# processor.net
KiCad netlist of a schematic drawn in Altium Designer
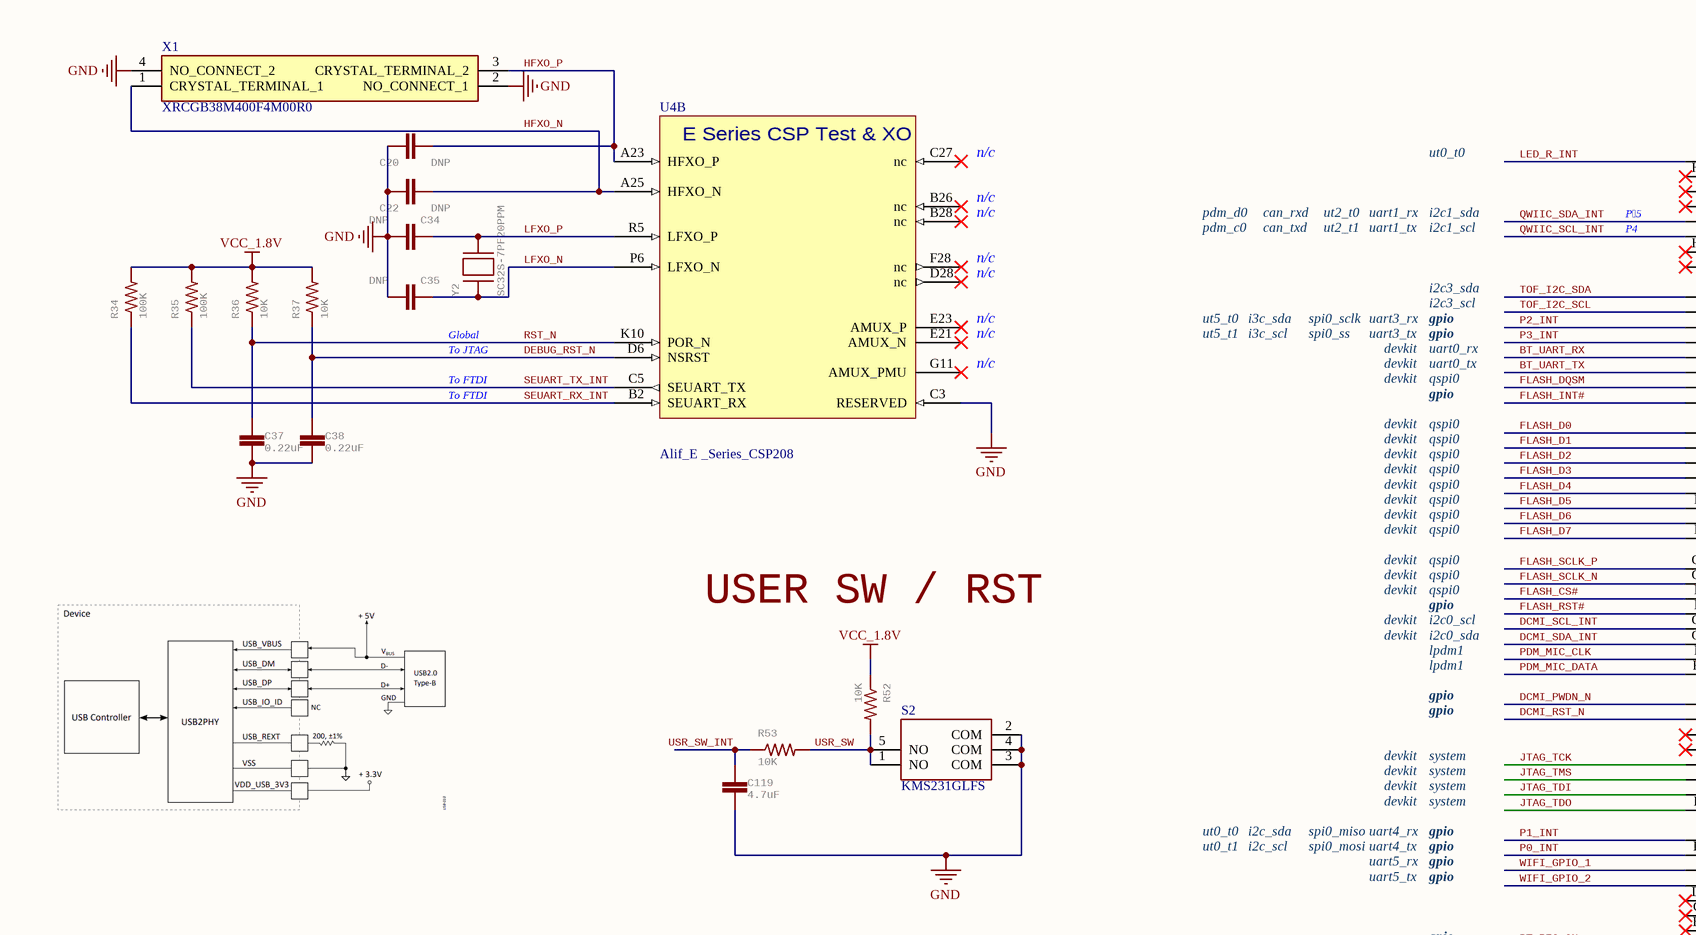
[diagram p0: processor.SchDoc, top left]
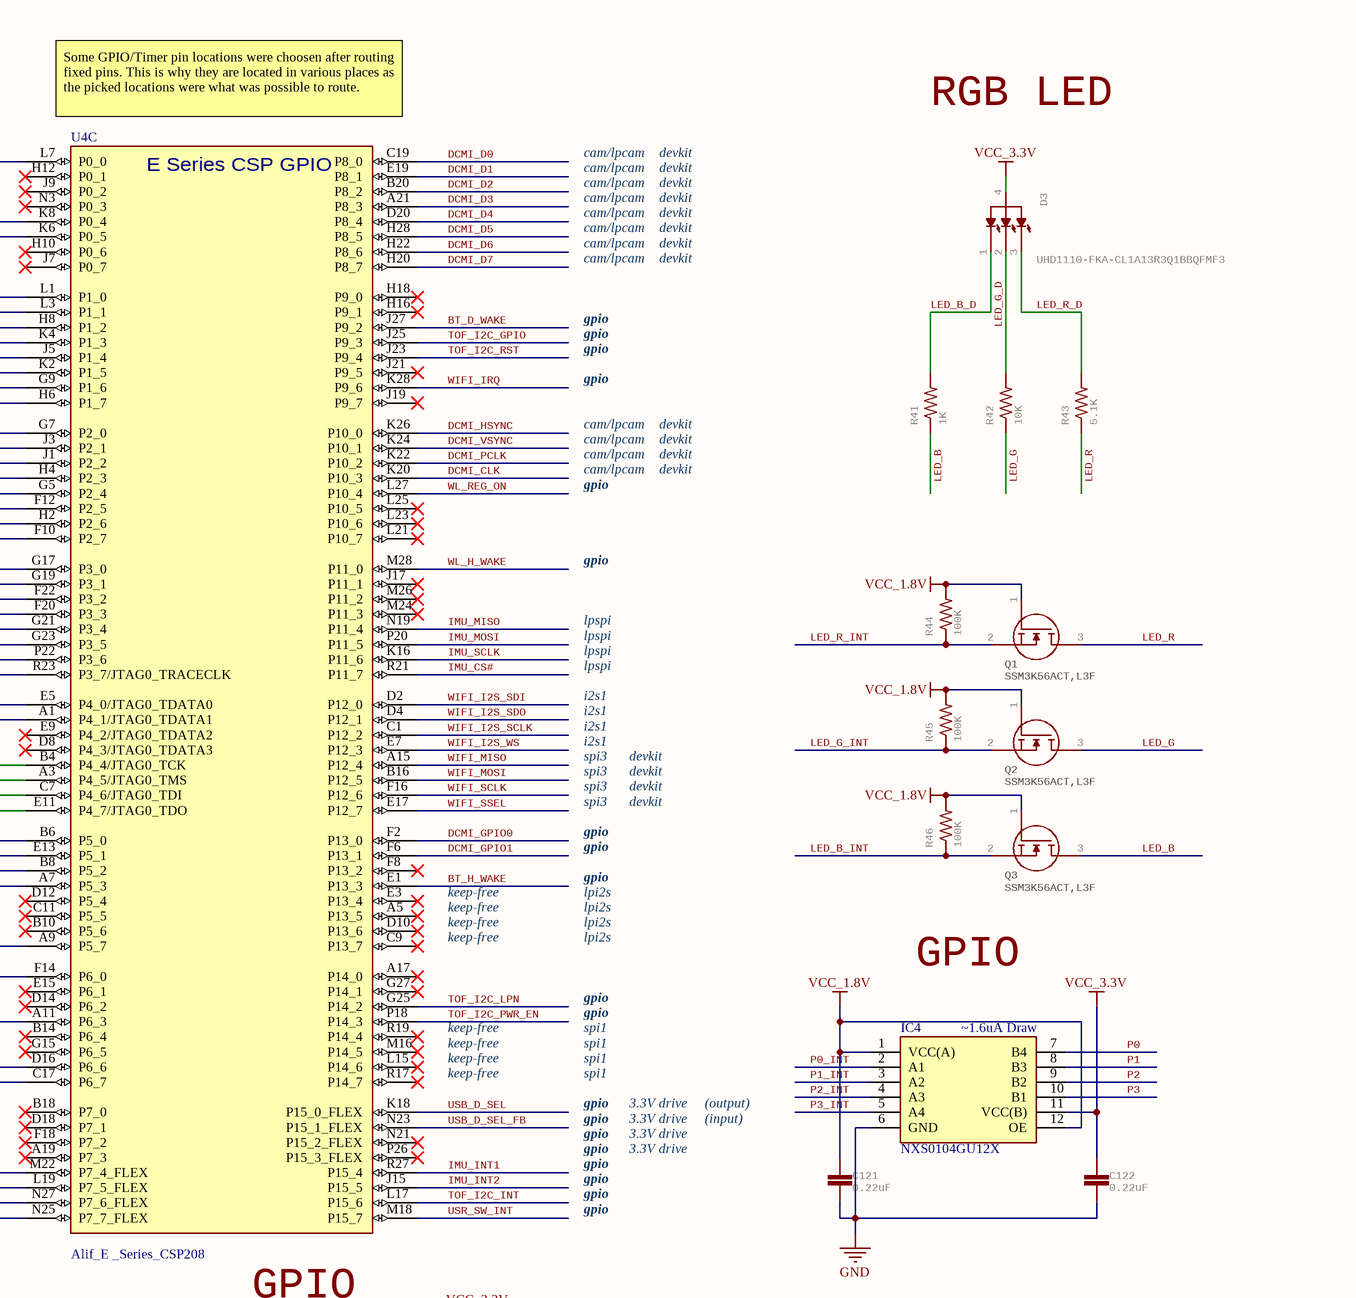
[diagram p1: processor.SchDoc, top right]
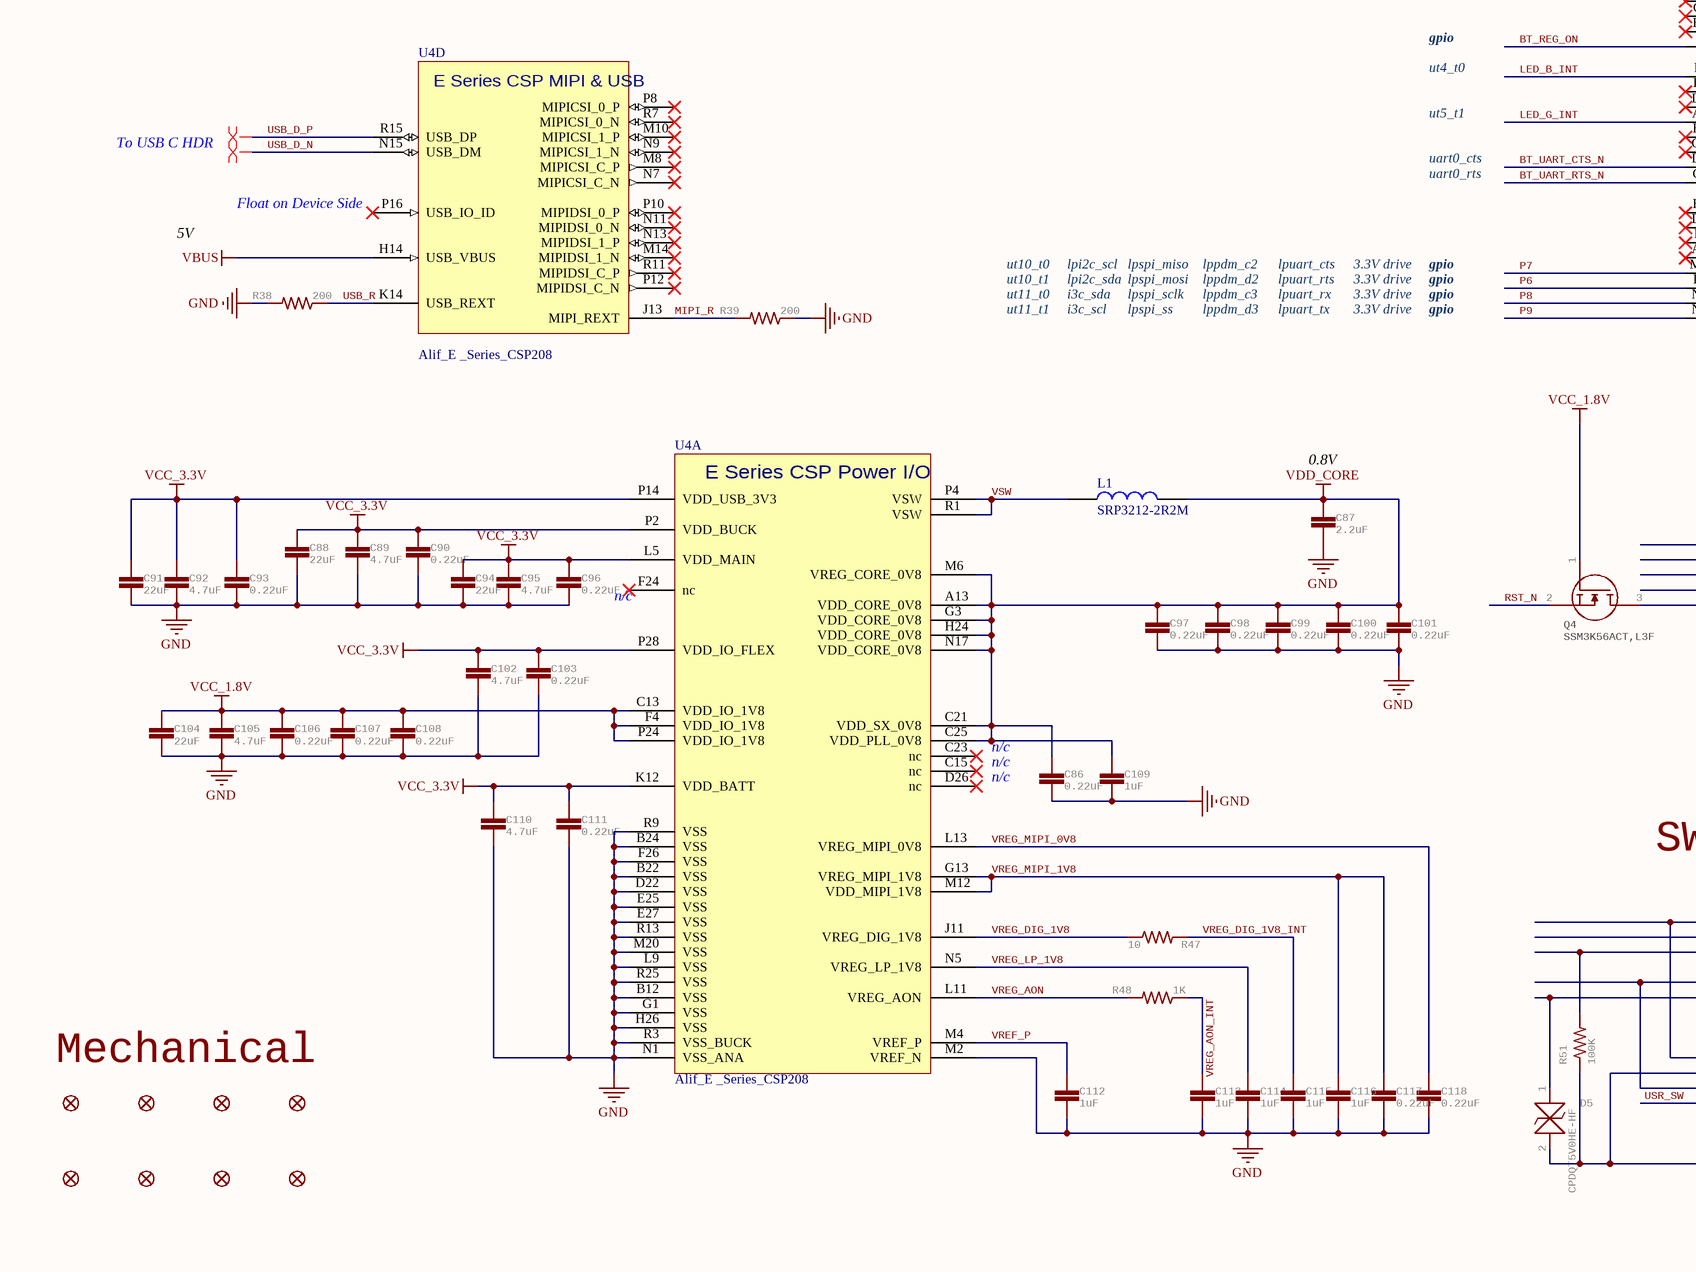
[diagram p2: processor.SchDoc, bottom left]
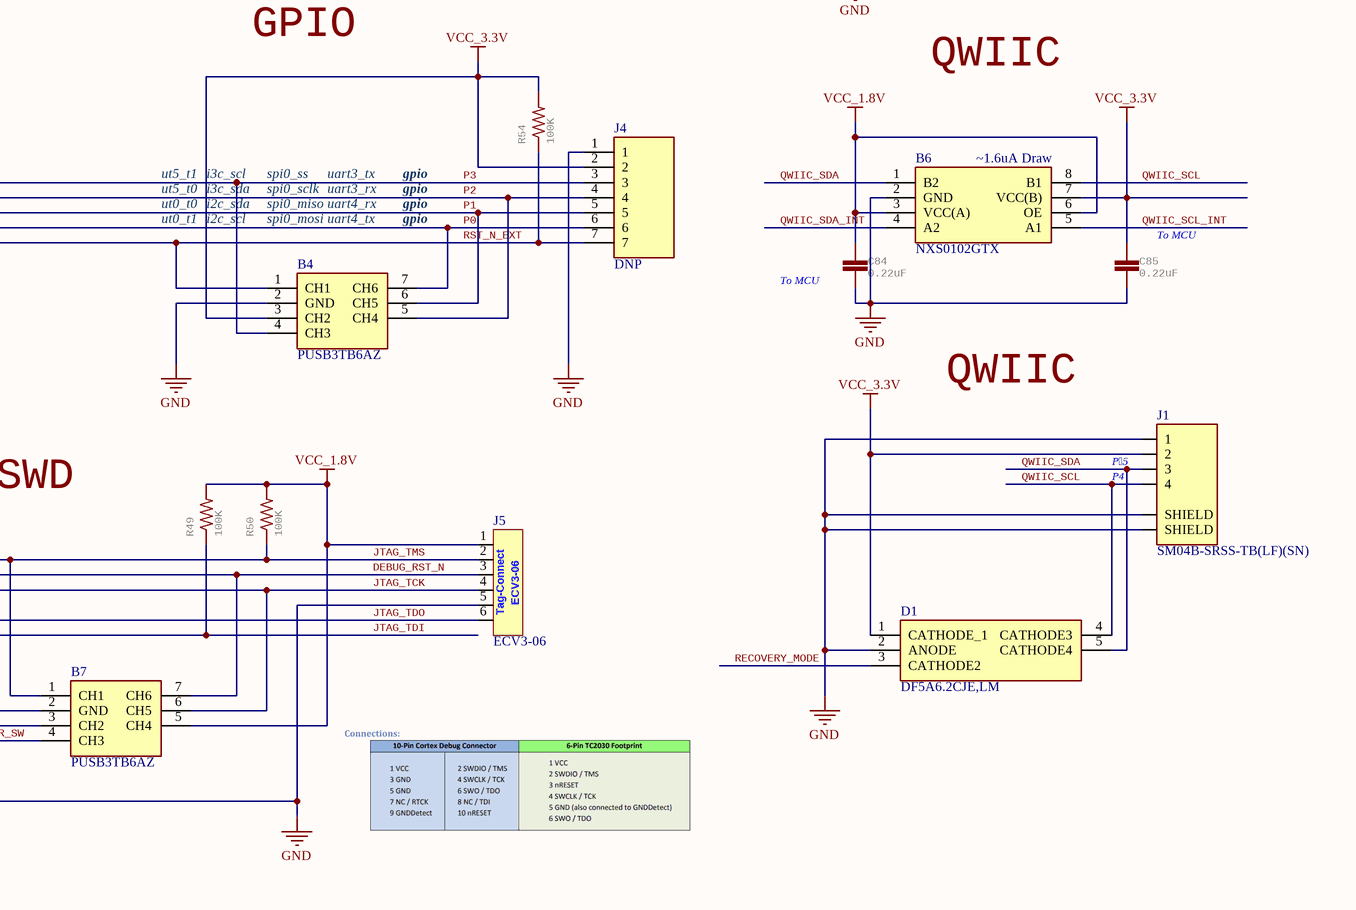
[diagram p3: processor.SchDoc, bottom right]

(export (version "E")
  (design (tool "Eeschema 10.0.6"))
  (components
    (comp (ref "B4")
      (value "PUSB3TB6AZ")
      (footprint "PUSB3TB6AZ")
      (description "NEXPERIA - PUSB3TB6AZ - DIODE, ESD PROTECTION, 5.5V, 0.27PF")
      (fields (field (name "MOUSER PART NUMBER") "771-PUSB3TB6AZ"))
      (libsource (lib "openmv-ae3") (part "PUSB3TB6AZ"))
    )
    (comp (ref "B6")
      (value "NXS0102GTX")
      (footprint "NXS0102GTX")
      (description "Dual supply translating transceiver; open drain; auto direction sensing")
      (fields (field (name "MOUSER PART NUMBER") "771-NXS0102GTX"))
      (libsource (lib "openmv-ae3") (part "NXS0102GTX"))
    )
    (comp (ref "B7")
      (value "PUSB3TB6AZ")
      (footprint "PUSB3TB6AZ")
      (description "NEXPERIA - PUSB3TB6AZ - DIODE, ESD PROTECTION, 5.5V, 0.27PF")
      (fields (field (name "MOUSER PART NUMBER") "771-PUSB3TB6AZ"))
      (libsource (lib "openmv-ae3") (part "PUSB3TB6AZ"))
    )
    (comp (ref "C20")
      (value "DNP")
      (footprint "C0201")
      (description "CAPACITOR, European symbol")
      (libsource (lib "") (part "C-EUC0201_2"))
    )
    (comp (ref "C22")
      (value "DNP")
      (footprint "C0201")
      (description "CAPACITOR, European symbol")
      (libsource (lib "") (part "C-EUC0201_2"))
    )
    (comp (ref "C34")
      (value "DNP")
      (footprint "C0201")
      (description "CAPACITOR, European symbol")
      (libsource (lib "") (part "C-EUC0201_1"))
    )
    (comp (ref "C35")
      (value "DNP")
      (footprint "C0201")
      (description "CAPACITOR, European symbol")
      (libsource (lib "") (part "C-EUC0201_1"))
    )
    (comp (ref "C37")
      (value "0.22uF")
      (footprint "C0201")
      (description "CAPACITOR, European symbol")
      (fields (field (name "MPN") "GRM033R60J224ME15D"))
      (libsource (lib "openmv-ae3") (part "C-EUC0201"))
    )
    (comp (ref "C38")
      (value "0.22uF")
      (footprint "C0201")
      (description "CAPACITOR, European symbol")
      (fields (field (name "MPN") "GRM033R60J224ME15D"))
      (libsource (lib "openmv-ae3") (part "C-EUC0201"))
    )
    (comp (ref "C84")
      (value "0.22uF")
      (footprint "C0201")
      (description "CAPACITOR, European symbol")
      (fields (field (name "MPN") "GRM033R60J224ME15D"))
      (libsource (lib "openmv-ae3") (part "C-EUC0201"))
    )
    (comp (ref "C85")
      (value "0.22uF")
      (footprint "C0201")
      (description "CAPACITOR, European symbol")
      (fields (field (name "MPN") "GRM033R60J224ME15D"))
      (libsource (lib "openmv-ae3") (part "C-EUC0201"))
    )
    (comp (ref "C86")
      (value "0.22uF")
      (footprint "C0201")
      (description "CAPACITOR, European symbol")
      (fields (field (name "MPN") "GRM033R60J224ME15D"))
      (libsource (lib "") (part "C-EUC0201_3"))
    )
    (comp (ref "C87")
      (value "2.2uF")
      (footprint "0402-CAP")
      (description "CapacitorStandard 0603 ceramic capacitor, and 0.1\" leaded capacitor.")
      (fields (field (name "MPN") "CL05A225MQ5NNNC") (field (name "LIBRARYNAME") "sfe"))
      (libsource (lib "openmv-ae3") (part "CAP0402-CAP"))
    )
    (comp (ref "C88")
      (value "22uF")
      (footprint "0805")
      (fields (field (name "MPN") "CL21A226MQQNNNE"))
      (libsource (lib "openmv-ae3") (part "22UF-0805-6.3V-20%"))
    )
    (comp (ref "C89")
      (value "4.7uF")
      (footprint "0402-CAP")
      (description "CapacitorStandard 0603 ceramic capacitor, and 0.1\" leaded capacitor.")
      (fields (field (name "MPN") "JMK105BBJ475MV-F") (field (name "LIBRARYNAME") "sfe"))
      (libsource (lib "openmv-ae3") (part "CAP0402-CAP"))
    )
    (comp (ref "C90")
      (value "0.22uF")
      (footprint "C0201")
      (description "CAPACITOR, European symbol")
      (fields (field (name "MPN") "GRM033R60J224ME15D"))
      (libsource (lib "openmv-ae3") (part "C-EUC0201"))
    )
    (comp (ref "C91")
      (value "22uF")
      (footprint "0805")
      (fields (field (name "MPN") "CL21A226MQQNNNE"))
      (libsource (lib "openmv-ae3") (part "22UF-0805-6.3V-20%"))
    )
    (comp (ref "C92")
      (value "4.7uF")
      (footprint "0402-CAP")
      (description "CapacitorStandard 0603 ceramic capacitor, and 0.1\" leaded capacitor.")
      (fields (field (name "MPN") "JMK105BBJ475MV-F") (field (name "LIBRARYNAME") "sfe"))
      (libsource (lib "openmv-ae3") (part "CAP0402-CAP"))
    )
    (comp (ref "C93")
      (value "0.22uF")
      (footprint "C0201")
      (description "CAPACITOR, European symbol")
      (fields (field (name "MPN") "GRM033R60J224ME15D"))
      (libsource (lib "openmv-ae3") (part "C-EUC0201"))
    )
    (comp (ref "C94")
      (value "22uF")
      (footprint "0805")
      (fields (field (name "MPN") "CL21A226MQQNNNE"))
      (libsource (lib "openmv-ae3") (part "22UF-0805-6.3V-20%"))
    )
    (comp (ref "C95")
      (value "4.7uF")
      (footprint "0402-CAP")
      (description "CapacitorStandard 0603 ceramic capacitor, and 0.1\" leaded capacitor.")
      (fields (field (name "MPN") "JMK105BBJ475MV-F") (field (name "LIBRARYNAME") "sfe"))
      (libsource (lib "openmv-ae3") (part "CAP0402-CAP"))
    )
    (comp (ref "C96")
      (value "0.22uF")
      (footprint "C0201")
      (description "CAPACITOR, European symbol")
      (fields (field (name "MPN") "GRM033R60J224ME15D"))
      (libsource (lib "openmv-ae3") (part "C-EUC0201"))
    )
    (comp (ref "C97")
      (value "0.22uF")
      (footprint "C0201")
      (description "CAPACITOR, European symbol")
      (fields (field (name "MPN") "GRM033R60J224ME15D"))
      (libsource (lib "openmv-ae3") (part "C-EUC0201"))
    )
    (comp (ref "C98")
      (value "0.22uF")
      (footprint "C0201")
      (description "CAPACITOR, European symbol")
      (fields (field (name "MPN") "GRM033R60J224ME15D"))
      (libsource (lib "openmv-ae3") (part "C-EUC0201"))
    )
    (comp (ref "C99")
      (value "0.22uF")
      (footprint "C0201")
      (description "CAPACITOR, European symbol")
      (fields (field (name "MPN") "GRM033R60J224ME15D"))
      (libsource (lib "openmv-ae3") (part "C-EUC0201"))
    )
    (comp (ref "C100")
      (value "0.22uF")
      (footprint "C0201")
      (description "CAPACITOR, European symbol")
      (fields (field (name "MPN") "GRM033R60J224ME15D"))
      (libsource (lib "openmv-ae3") (part "C-EUC0201"))
    )
    (comp (ref "C101")
      (value "0.22uF")
      (footprint "C0201")
      (description "CAPACITOR, European symbol")
      (fields (field (name "MPN") "GRM033R60J224ME15D"))
      (libsource (lib "openmv-ae3") (part "C-EUC0201"))
    )
    (comp (ref "C102")
      (value "4.7uF")
      (footprint "0402-CAP")
      (description "CapacitorStandard 0603 ceramic capacitor, and 0.1\" leaded capacitor.")
      (fields (field (name "MPN") "JMK105BBJ475MV-F") (field (name "LIBRARYNAME") "sfe"))
      (libsource (lib "openmv-ae3") (part "CAP0402-CAP"))
    )
    (comp (ref "C103")
      (value "0.22uF")
      (footprint "C0201")
      (description "CAPACITOR, European symbol")
      (fields (field (name "MPN") "GRM033R60J224ME15D"))
      (libsource (lib "openmv-ae3") (part "C-EUC0201"))
    )
    (comp (ref "C104")
      (value "22uF")
      (footprint "0805")
      (fields (field (name "MPN") "CL21A226MQQNNNE"))
      (libsource (lib "openmv-ae3") (part "22UF-0805-6.3V-20%"))
    )
    (comp (ref "C105")
      (value "4.7uF")
      (footprint "0402-CAP")
      (description "CapacitorStandard 0603 ceramic capacitor, and 0.1\" leaded capacitor.")
      (fields (field (name "MPN") "JMK105BBJ475MV-F") (field (name "LIBRARYNAME") "sfe"))
      (libsource (lib "openmv-ae3") (part "CAP0402-CAP"))
    )
    (comp (ref "C106")
      (value "0.22uF")
      (footprint "C0201")
      (description "CAPACITOR, European symbol")
      (fields (field (name "MPN") "GRM033R60J224ME15D"))
      (libsource (lib "openmv-ae3") (part "C-EUC0201"))
    )
    (comp (ref "C107")
      (value "0.22uF")
      (footprint "C0201")
      (description "CAPACITOR, European symbol")
      (fields (field (name "MPN") "GRM033R60J224ME15D"))
      (libsource (lib "openmv-ae3") (part "C-EUC0201"))
    )
    (comp (ref "C108")
      (value "0.22uF")
      (footprint "C0201")
      (description "CAPACITOR, European symbol")
      (fields (field (name "MPN") "GRM033R60J224ME15D"))
      (libsource (lib "openmv-ae3") (part "C-EUC0201"))
    )
    (comp (ref "C109")
      (value "1uF")
      (footprint "C0201")
      (description "CAPACITOR, European symbol")
      (fields (field (name "MPN") "CL03A105MQ3CSNC"))
      (libsource (lib "") (part "C-EUC0201_3"))
    )
    (comp (ref "C110")
      (value "4.7uF")
      (footprint "0402-CAP")
      (description "CapacitorStandard 0603 ceramic capacitor, and 0.1\" leaded capacitor.")
      (fields (field (name "MPN") "JMK105BBJ475MV-F") (field (name "LIBRARYNAME") "sfe"))
      (libsource (lib "openmv-ae3") (part "CAP0402-CAP"))
    )
    (comp (ref "C111")
      (value "0.22uF")
      (footprint "C0201")
      (description "CAPACITOR, European symbol")
      (fields (field (name "MPN") "GRM033R60J224ME15D"))
      (libsource (lib "openmv-ae3") (part "C-EUC0201"))
    )
    (comp (ref "C112")
      (value "1uF")
      (footprint "C0201")
      (description "CAPACITOR, European symbol")
      (fields (field (name "MPN") "CL03A105MQ3CSNC"))
      (libsource (lib "openmv-ae3") (part "C-EUC0201"))
    )
    (comp (ref "C113")
      (value "1uF")
      (footprint "C0201")
      (description "CAPACITOR, European symbol")
      (fields (field (name "MPN") "CL03A105MQ3CSNC"))
      (libsource (lib "openmv-ae3") (part "C-EUC0201"))
    )
    (comp (ref "C114")
      (value "1uF")
      (footprint "C0201")
      (description "CAPACITOR, European symbol")
      (fields (field (name "MPN") "CL03A105MQ3CSNC"))
      (libsource (lib "openmv-ae3") (part "C-EUC0201"))
    )
    (comp (ref "C115")
      (value "1uF")
      (footprint "C0201")
      (description "CAPACITOR, European symbol")
      (fields (field (name "MPN") "CL03A105MQ3CSNC"))
      (libsource (lib "openmv-ae3") (part "C-EUC0201"))
    )
    (comp (ref "C116")
      (value "1uF")
      (footprint "C0201")
      (description "CAPACITOR, European symbol")
      (fields (field (name "MPN") "CL03A105MQ3CSNC"))
      (libsource (lib "openmv-ae3") (part "C-EUC0201"))
    )
    (comp (ref "C117")
      (value "0.22uF")
      (footprint "C0201")
      (description "CAPACITOR, European symbol")
      (fields (field (name "MPN") "GRM033R60J224ME15D"))
      (libsource (lib "openmv-ae3") (part "C-EUC0201"))
    )
    (comp (ref "C118")
      (value "0.22uF")
      (footprint "C0201")
      (description "CAPACITOR, European symbol")
      (fields (field (name "MPN") "GRM033R60J224ME15D"))
      (libsource (lib "openmv-ae3") (part "C-EUC0201"))
    )
    (comp (ref "C119")
      (value "4.7uF")
      (footprint "0402-CAP")
      (description "CapacitorStandard 0603 ceramic capacitor, and 0.1\" leaded capacitor.")
      (fields (field (name "MPN") "JMK105BBJ475MV-F") (field (name "LIBRARYNAME") "sfe"))
      (libsource (lib "openmv-ae3") (part "CAP0402-CAP"))
    )
    (comp (ref "C121")
      (value "0.22uF")
      (footprint "C0201")
      (description "CAPACITOR, European symbol")
      (fields (field (name "MPN") "GRM033R60J224ME15D"))
      (libsource (lib "openmv-ae3") (part "C-EUC0201"))
    )
    (comp (ref "C122")
      (value "0.22uF")
      (footprint "C0201")
      (description "CAPACITOR, European symbol")
      (fields (field (name "MPN") "GRM033R60J224ME15D"))
      (libsource (lib "openmv-ae3") (part "C-EUC0201"))
    )
    (comp (ref "D1")
      (value "DF5A6.2CJE,LM")
      (footprint "SamacSys:SOTFL50P160X60-5N")
      (description "Diode")
      (fields (field (name "MOUSER PART NUMBER") "757-DF5A6.2CJE,LM"))
      (libsource (lib "openmv-ae3") (part "DF5A5.6CJE,LM"))
    )
    (comp (ref "D3")
      (value "UHD1110-FKA-CL1A13R3Q1BBQFMF3")
      (footprint "LED_UHD1110-FKA-CL1A13R3Q1BBQFMF3")
      (description "LED RGB SMD, SIZE 1 X 1 mm Check availability")
      (fields (field (name "MF") "Cree Inc.") (field (name "MPN") "UHD1110-FKA-CL1A13r3q1BBQFMF3"))
      (libsource (lib "openmv-ae3") (part "UHD1110-FKA-CL1A13R3Q1BBQFMF3"))
    )
    (comp (ref "D5")
      (value "CPDQT5V0HE-HF")
      (footprint "CPDQT5V0HEHF")
      (description "ESD Suppressors / TVS Diodes DIODE ESD 5VWM 65W 0402/SOD-923F   Source:  Datasheet")
      (fields (field (name "MOUSER_PART_NUMBER") "MOUSER_PART_NUMBER"))
      (libsource (lib "openmv-ae3") (part "CPDQT5V0HE-HF"))
    )
    (comp (ref "FD1")
      (value "FIDUCIAL1X2")
      (footprint "FIDUCIAL-1X2")
      (fields (field (name "LIBRARYNAME") "SparkFun-Aesthetics"))
      (libsource (lib "openmv-ae3") (part "FIDUCIAL1X2"))
    )
    (comp (ref "FD2")
      (value "FIDUCIAL1X2")
      (footprint "FIDUCIAL-1X2")
      (fields (field (name "LIBRARYNAME") "SparkFun-Aesthetics"))
      (libsource (lib "openmv-ae3") (part "FIDUCIAL1X2"))
    )
    (comp (ref "FD3")
      (value "FIDUCIAL1X2")
      (footprint "FIDUCIAL-1X2")
      (fields (field (name "LIBRARYNAME") "SparkFun-Aesthetics"))
      (libsource (lib "openmv-ae3") (part "FIDUCIAL1X2"))
    )
    (comp (ref "FD4")
      (value "FIDUCIAL1X2")
      (footprint "FIDUCIAL-1X2")
      (fields (field (name "LIBRARYNAME") "SparkFun-Aesthetics"))
      (libsource (lib "openmv-ae3") (part "FIDUCIAL1X2"))
    )
    (comp (ref "FD5")
      (value "FIDUCIAL1X2")
      (footprint "FIDUCIAL-1X2")
      (fields (field (name "LIBRARYNAME") "SparkFun-Aesthetics"))
      (libsource (lib "openmv-ae3") (part "FIDUCIAL1X2"))
    )
    (comp (ref "FD6")
      (value "FIDUCIAL1X2")
      (footprint "FIDUCIAL-1X2")
      (fields (field (name "LIBRARYNAME") "SparkFun-Aesthetics"))
      (libsource (lib "openmv-ae3") (part "FIDUCIAL1X2"))
    )
    (comp (ref "FD7")
      (value "FIDUCIAL1X2")
      (footprint "FIDUCIAL-1X2")
      (fields (field (name "LIBRARYNAME") "SparkFun-Aesthetics"))
      (libsource (lib "openmv-ae3") (part "FIDUCIAL1X2"))
    )
    (comp (ref "FD8")
      (value "FIDUCIAL1X2")
      (footprint "FIDUCIAL-1X2")
      (fields (field (name "LIBRARYNAME") "SparkFun-Aesthetics"))
      (libsource (lib "openmv-ae3") (part "FIDUCIAL1X2"))
    )
    (comp (ref "IC4")
      (value "NXS0104GU12X")
      (footprint "SamacSys:NXS0104GU12X")
      (description "Integrated Circuit")
      (fields (field (name "MOUSER PART NUMBER") "771-NXS0104GU12X"))
      (libsource (lib "*") (part "NXS0104GU12X"))
    )
    (comp (ref "J1")
      (value "SM04B-SRSS-TB(LF)(SN)")
      (footprint "JST_SM04B-SRSS-TB(LF)(SN)")
      (description "SH Series 1.0 mm Pitch 2 Position Single Row Side Entry Shrouded Header")
      (libsource (lib "openmv-ae3") (part "SM04B-SRSS-TB(LF)(SN)"))
    )
    (comp (ref "J4")
      (value "DNP")
      (footprint "SamacSys:HDRV7W66P0X254_1X7_1778X254X844P")
      (description "Connector")
      (fields
        (field (name "MANUFACTURER_PART_NUMBER") "M20-9770746")
        (field (name "MOUSER PART NUMBER") "855-M20-9770746")
      )
      (libsource (lib "openmv-ae3") (part "M20-9770746"))
    )
    (comp (ref "J5")
      (value "ECV3-06")
      (footprint "Tag-Connect-ECV3-Footprints:ECV3-06")
      (description "Tag-Connect Edge-Connect ECV3-06 No-Solder Debug Castellated Pads Connector DO NOT PLACE NO BOM")
      (libsource (lib "openmv-ae3") (part "ECV3-06"))
    )
    (comp (ref "L1")
      (value "SRP3212-2R2M")
      (footprint "IND3225X100N")
      (description "Ind,3.2x2.5x1mm,2.2uH?20%,4A,shd")
      (fields (field (name "MOUSER PART NUMBER") "652-SRP3212-2R2M"))
      (libsource (lib "openmv-ae3") (part "SRP3212-2R2M"))
    )
    (comp (ref "Q1")
      (value "NMOS")
      (footprint "DFN1006")
      (fields (field (name "MPN") "SSM3K56ACT,L3F") (field (name "PART NUMBER") "SSM3K56ACT,L3F"))
      (libsource (lib "openmv-ae3") (part "NMOS"))
    )
    (comp (ref "Q2")
      (value "NMOS")
      (footprint "DFN1006")
      (fields (field (name "MPN") "SSM3K56ACT,L3F") (field (name "PART NUMBER") "SSM3K56ACT,L3F"))
      (libsource (lib "openmv-ae3") (part "NMOS"))
    )
    (comp (ref "Q3")
      (value "NMOS")
      (footprint "DFN1006")
      (fields (field (name "MPN") "SSM3K56ACT,L3F") (field (name "PART NUMBER") "SSM3K56ACT,L3F"))
      (libsource (lib "openmv-ae3") (part "NMOS"))
    )
    (comp (ref "Q4")
      (value "NMOS")
      (footprint "DFN1006")
      (fields (field (name "MPN") "SSM3K56ACT,L3F") (field (name "PART NUMBER") "SSM3K56ACT,L3F"))
      (libsource (lib "openmv-ae3") (part "NMOS"))
    )
    (comp (ref "R34")
      (value "100K")
      (footprint "R0201")
      (fields (field (name "MPN") "RMCF0201FT100K") (field (name "LIBRARYNAME") "sfe"))
      (libsource (lib "openmv-ae3") (part "RESISTOR0402-RES"))
    )
    (comp (ref "R35")
      (value "100K")
      (footprint "R0201")
      (fields (field (name "MPN") "RMCF0201FT100K") (field (name "LIBRARYNAME") "sfe"))
      (libsource (lib "openmv-ae3") (part "RESISTOR0402-RES"))
    )
    (comp (ref "R36")
      (value "10K")
      (footprint "R0201")
      (fields (field (name "MPN") "RMCF0201FT10K0") (field (name "LIBRARYNAME") "sfe"))
      (libsource (lib "openmv-ae3") (part "RESISTOR0402-RES"))
    )
    (comp (ref "R37")
      (value "10K")
      (footprint "R0201")
      (fields (field (name "MPN") "RMCF0201FT10K0") (field (name "LIBRARYNAME") "sfe"))
      (libsource (lib "openmv-ae3") (part "RESISTOR0402-RES"))
    )
    (comp (ref "R38")
      (value "200")
      (footprint "R0201")
      (fields (field (name "MPN") "CR0201-FW-2000GLF") (field (name "LIBRARYNAME") "sfe"))
      (libsource (lib "openmv-ae3") (part "RESISTOR0402-RES"))
    )
    (comp (ref "R39")
      (value "200")
      (footprint "R0201")
      (fields (field (name "MPN") "CR0201-FW-2000GLF") (field (name "LIBRARYNAME") "sfe"))
      (libsource (lib "openmv-ae3") (part "RESISTOR0402-RES"))
    )
    (comp (ref "R41")
      (value "1K")
      (footprint "R0201")
      (description "ResistorBasic schematic elements and footprints for 0603, 1206, and PTH resistors.")
      (fields (field (name "MPN") "RMCF0201FT1K00") (field (name "LIBRARYNAME") "sfe"))
      (libsource (lib "openmv-ae3") (part "RESISTOR0402-RES"))
    )
    (comp (ref "R42")
      (value "10K")
      (footprint "R0201")
      (description "ResistorBasic schematic elements and footprints for 0603, 1206, and PTH resistors.")
      (fields (field (name "MPN") "RMCF0201FT10K0") (field (name "LIBRARYNAME") "sfe"))
      (libsource (lib "openmv-ae3") (part "RESISTOR0402-RES"))
    )
    (comp (ref "R43")
      (value "5.1K")
      (footprint "R0201")
      (description "ResistorBasic schematic elements and footprints for 0603, 1206, and PTH resistors.")
      (fields (field (name "MPN") "AC0201FR-075K1L") (field (name "LIBRARYNAME") "sfe"))
      (libsource (lib "openmv-ae3") (part "RESISTOR0402-RES"))
    )
    (comp (ref "R44")
      (value "100K")
      (footprint "R0201")
      (fields (field (name "MPN") "RMCF0201FT100K") (field (name "LIBRARYNAME") "sfe"))
      (libsource (lib "openmv-ae3") (part "RESISTOR0402-RES"))
    )
    (comp (ref "R45")
      (value "100K")
      (footprint "R0201")
      (fields (field (name "MPN") "RMCF0201FT100K") (field (name "LIBRARYNAME") "sfe"))
      (libsource (lib "openmv-ae3") (part "RESISTOR0402-RES"))
    )
    (comp (ref "R46")
      (value "100K")
      (footprint "R0201")
      (fields (field (name "MPN") "RMCF0201FT100K") (field (name "LIBRARYNAME") "sfe"))
      (libsource (lib "openmv-ae3") (part "RESISTOR0402-RES"))
    )
    (comp (ref "R47")
      (value "10")
      (footprint "R0201")
      (fields (field (name "MPN") "RMCF0201JT10R0") (field (name "LIBRARYNAME") "sfe"))
      (libsource (lib "openmv-ae3") (part "RESISTOR0402-RES"))
    )
    (comp (ref "R48")
      (value "1K")
      (footprint "R0201")
      (fields (field (name "MPN") "RMCF0201FT1K00") (field (name "LIBRARYNAME") "sfe"))
      (libsource (lib "openmv-ae3") (part "RESISTOR0402-RES"))
    )
    (comp (ref "R49")
      (value "100K")
      (footprint "R0201")
      (fields (field (name "MPN") "RMCF0201FT100K") (field (name "LIBRARYNAME") "sfe"))
      (libsource (lib "openmv-ae3") (part "RESISTOR0402-RES"))
    )
    (comp (ref "R50")
      (value "100K")
      (footprint "R0201")
      (fields (field (name "MPN") "RMCF0201FT100K") (field (name "LIBRARYNAME") "sfe"))
      (libsource (lib "openmv-ae3") (part "RESISTOR0402-RES"))
    )
    (comp (ref "R51")
      (value "100K")
      (footprint "R0201")
      (fields (field (name "MPN") "RMCF0201FT100K") (field (name "LIBRARYNAME") "sfe"))
      (libsource (lib "openmv-ae3") (part "RESISTOR0402-RES"))
    )
    (comp (ref "R52")
      (value "10K")
      (footprint "R0201")
      (fields (field (name "MPN") "RMCF0201FT10K0") (field (name "LIBRARYNAME") "sfe"))
      (libsource (lib "openmv-ae3") (part "RESISTOR0402-RES"))
    )
    (comp (ref "R53")
      (value "10K")
      (footprint "R0201")
      (fields (field (name "MPN") "RMCF0201FT10K0") (field (name "LIBRARYNAME") "sfe"))
      (libsource (lib "openmv-ae3") (part "RESISTOR0402-RES"))
    )
    (comp (ref "R54")
      (value "100K")
      (footprint "R0201")
      (fields (field (name "MPN") "RMCF0201FT100K") (field (name "LIBRARYNAME") "sfe"))
      (libsource (lib "openmv-ae3") (part "RESISTOR0402-RES"))
    )
    (comp (ref "S2")
      (value "KMS231GLFS")
      (footprint "KMS231GLFS")
      (libsource (lib "openmv-ae3") (part "KMS231GLFS"))
    )
    (comp (ref "U4")
      (value "Alif_E _Series_CSP208")
      (footprint "CSP208")
      (description "IC,Alif E7 MCU, Rev B silicon,CSP208")
      (fields (field (name "MPN") "AE302F80F55D5AE"))
      (libsource (lib "openmv-ae3") (part "E7_B0_CSP_208"))
    )
    (comp (ref "X1")
      (value "XRCGB38M400F4M00R0")
      (footprint "XTAL_2016")
      (description "2.0X1.6X0.65MM 38.4MHZ CRYSTAL")
      (libsource (lib "openmv-ae3") (part "XRCGB38M400F4M00R0"))
    )
    (comp (ref "Y2")
      (value "SC32S-7PF20PPM")
      (footprint "XTAL_ABS07-32.768KHZ-7-T")
      (description "Check availability")
      (fields (field (name "MF") "Abracon") (field (name "MP") "ABS07-32.768KHZ-7-T"))
      (libsource (lib "openmv-ae3") (part "ABS07-32.768KHZ-7-T"))
    )
  )
  (nets
    (net (code "1") (name "/BT_D_WAKE") (class "Default")
      (node (ref "U4") (pin "J27") (pinfunction "P9_2_J27") (pintype "bidirectional"))
    )
    (net (code "2") (name "/BT_H_WAKE") (class "Default")
      (node (ref "U4") (pin "E1") (pinfunction "P13_3_E1") (pintype "bidirectional"))
    )
    (net (code "3") (name "/BT_REG_ON") (class "Default")
      (node (ref "U4") (pin "A9") (pinfunction "P5_7_A9") (pintype "bidirectional"))
    )
    (net (code "4") (name "/BT_UART_CTS_N") (class "Default")
      (node (ref "U4") (pin "D16") (pinfunction "P6_6_D16") (pintype "bidirectional"))
    )
    (net (code "5") (name "/BT_UART_RTS_N") (class "Default")
      (node (ref "U4") (pin "C17") (pinfunction "P6_7_C17") (pintype "bidirectional"))
    )
    (net (code "6") (name "/BT_UART_RX") (class "Default")
      (node (ref "U4") (pin "J5") (pinfunction "P1_4_J5") (pintype "bidirectional"))
    )
    (net (code "7") (name "/BT_UART_TX") (class "Default")
      (node (ref "U4") (pin "K2") (pinfunction "P1_5_K2") (pintype "bidirectional"))
    )
    (net (code "8") (name "/DCMI_CLK") (class "Default")
      (node (ref "U4") (pin "K20") (pinfunction "P10_3_K20") (pintype "bidirectional"))
    )
    (net (code "9") (name "/DCMI_D0") (class "Default")
      (node (ref "U4") (pin "C19") (pinfunction "P8_0_C19") (pintype "bidirectional"))
    )
    (net (code "10") (name "/DCMI_D1") (class "Default")
      (node (ref "U4") (pin "E19") (pinfunction "P8_1_E19") (pintype "bidirectional"))
    )
    (net (code "11") (name "/DCMI_D2") (class "Default")
      (node (ref "U4") (pin "B20") (pinfunction "P8_2_B20") (pintype "bidirectional"))
    )
    (net (code "12") (name "/DCMI_D3") (class "Default")
      (node (ref "U4") (pin "A21") (pinfunction "P8_3_A21") (pintype "bidirectional"))
    )
    (net (code "13") (name "/DCMI_D4") (class "Default")
      (node (ref "U4") (pin "D20") (pinfunction "P8_4_D20") (pintype "bidirectional"))
    )
    (net (code "14") (name "/DCMI_D5") (class "Default")
      (node (ref "U4") (pin "H28") (pinfunction "P8_5_H28") (pintype "bidirectional"))
    )
    (net (code "15") (name "/DCMI_D6") (class "Default")
      (node (ref "U4") (pin "H22") (pinfunction "P8_6_H22") (pintype "bidirectional"))
    )
    (net (code "16") (name "/DCMI_D7") (class "Default")
      (node (ref "U4") (pin "H20") (pinfunction "P8_7_H20") (pintype "bidirectional"))
    )
    (net (code "17") (name "/DCMI_GPIO0") (class "Default")
      (node (ref "U4") (pin "F2") (pinfunction "P13_0_F2") (pintype "bidirectional"))
    )
    (net (code "18") (name "/DCMI_GPIO1") (class "Default")
      (node (ref "U4") (pin "F6") (pinfunction "P13_1_F6") (pintype "bidirectional"))
    )
    (net (code "19") (name "/DCMI_HSYNC") (class "Default")
      (node (ref "U4") (pin "K26") (pinfunction "P10_0_K26") (pintype "bidirectional"))
    )
    (net (code "20") (name "/DCMI_PCLK") (class "Default")
      (node (ref "U4") (pin "K22") (pinfunction "P10_2_K22") (pintype "bidirectional"))
    )
    (net (code "21") (name "/DCMI_PWDN_N") (class "Default")
      (node (ref "U4") (pin "E5") (pinfunction "P4_0/JTAG0_TDATA0_E5") (pintype "bidirectional"))
    )
    (net (code "22") (name "/DCMI_RST_N") (class "Default")
      (node (ref "U4") (pin "A1") (pinfunction "P4_1/JTAG0_TDATA1_A1") (pintype "bidirectional"))
    )
    (net (code "23") (name "/DCMI_SCL_INT") (class "Default")
      (node (ref "U4") (pin "G21") (pinfunction "P3_4_G21") (pintype "bidirectional"))
    )
    (net (code "24") (name "/DCMI_SDA_INT") (class "Default")
      (node (ref "U4") (pin "G23") (pinfunction "P3_5_G23") (pintype "bidirectional"))
    )
    (net (code "25") (name "/DCMI_VSYNC") (class "Default")
      (node (ref "U4") (pin "K24") (pinfunction "P10_1_K24") (pintype "bidirectional"))
    )
    (net (code "26") (name "/DEBUG_RST_N") (class "Default")
      (node (ref "B7") (pin "7") (pinfunction "CH6_7") (pintype "passive"))
      (node (ref "C38") (pin "2") (pinfunction "2_2") (pintype "passive"))
      (node (ref "J5") (pin "3") (pintype "passive"))
      (node (ref "R37") (pin "1") (pinfunction "1_1") (pintype "passive"))
      (node (ref "U4") (pin "D6") (pinfunction "NSRST_D6") (pintype "input"))
    )
    (net (code "27") (name "/FLASH_CS#") (class "Default")
      (node (ref "U4") (pin "F22") (pinfunction "P3_2_F22") (pintype "bidirectional"))
    )
    (net (code "28") (name "/FLASH_D0") (class "Default")
      (node (ref "U4") (pin "G7") (pinfunction "P2_0_G7") (pintype "bidirectional"))
    )
    (net (code "29") (name "/FLASH_D1") (class "Default")
      (node (ref "U4") (pin "J3") (pinfunction "P2_1_J3") (pintype "bidirectional"))
    )
    (net (code "30") (name "/FLASH_D2") (class "Default")
      (node (ref "U4") (pin "J1") (pinfunction "P2_2_J1") (pintype "bidirectional"))
    )
    (net (code "31") (name "/FLASH_D3") (class "Default")
      (node (ref "U4") (pin "H4") (pinfunction "P2_3_H4") (pintype "bidirectional"))
    )
    (net (code "32") (name "/FLASH_D4") (class "Default")
      (node (ref "U4") (pin "G5") (pinfunction "P2_4_G5") (pintype "bidirectional"))
    )
    (net (code "33") (name "/FLASH_D5") (class "Default")
      (node (ref "U4") (pin "F12") (pinfunction "P2_5_F12") (pintype "bidirectional"))
    )
    (net (code "34") (name "/FLASH_D6") (class "Default")
      (node (ref "U4") (pin "H2") (pinfunction "P2_6_H2") (pintype "bidirectional"))
    )
    (net (code "35") (name "/FLASH_D7") (class "Default")
      (node (ref "U4") (pin "F10") (pinfunction "P2_7_F10") (pintype "bidirectional"))
    )
    (net (code "36") (name "/FLASH_DQSM") (class "Default")
      (node (ref "U4") (pin "G9") (pinfunction "P1_6_G9") (pintype "bidirectional"))
    )
    (net (code "37") (name "/FLASH_INT#") (class "Default")
      (node (ref "U4") (pin "H6") (pinfunction "P1_7_H6") (pintype "bidirectional"))
    )
    (net (code "38") (name "/FLASH_RST#") (class "Default")
      (node (ref "U4") (pin "F20") (pinfunction "P3_3_F20") (pintype "bidirectional"))
    )
    (net (code "39") (name "/FLASH_SCLK_N") (class "Default")
      (node (ref "U4") (pin "G19") (pinfunction "P3_1_G19") (pintype "bidirectional"))
    )
    (net (code "40") (name "/FLASH_SCLK_P") (class "Default")
      (node (ref "U4") (pin "G17") (pinfunction "P3_0_G17") (pintype "bidirectional"))
    )
    (net (code "41") (name "/HFXO_N") (class "Default")
      (node (ref "C22") (pin "2") (pinfunction "2_2") (pintype "passive"))
      (node (ref "U4") (pin "A25") (pinfunction "HFXO_N_A25") (pintype "input"))
      (node (ref "X1") (pin "1") (pinfunction "CRYSTAL_TERMINAL_1_1") (pintype "passive"))
    )
    (net (code "42") (name "/HFXO_P") (class "Default")
      (node (ref "C20") (pin "2") (pinfunction "2_2") (pintype "passive"))
      (node (ref "U4") (pin "A23") (pinfunction "HFXO_P_A23") (pintype "input"))
      (node (ref "X1") (pin "3") (pinfunction "CRYSTAL_TERMINAL_2_3") (pintype "passive"))
    )
    (net (code "43") (name "/IMU_CS#") (class "Default")
      (node (ref "U4") (pin "R21") (pinfunction "P11_7_R21") (pintype "bidirectional"))
    )
    (net (code "44") (name "/IMU_INT1") (class "Default")
      (node (ref "U4") (pin "R27") (pinfunction "P15_4_R27") (pintype "bidirectional"))
    )
    (net (code "45") (name "/IMU_INT2") (class "Default")
      (node (ref "U4") (pin "J15") (pinfunction "P15_5_J15") (pintype "bidirectional"))
    )
    (net (code "46") (name "/IMU_MISO") (class "Default")
      (node (ref "U4") (pin "N19") (pinfunction "P11_4_N19") (pintype "bidirectional"))
    )
    (net (code "47") (name "/IMU_MOSI") (class "Default")
      (node (ref "U4") (pin "P20") (pinfunction "P11_5_P20") (pintype "bidirectional"))
    )
    (net (code "48") (name "/IMU_SCLK") (class "Default")
      (node (ref "U4") (pin "K16") (pinfunction "P11_6_K16") (pintype "bidirectional"))
    )
    (net (code "49") (name "/JTAG_TCK") (class "Default")
      (node (ref "B7") (pin "6") (pinfunction "CH5_6") (pintype "passive"))
      (node (ref "J5") (pin "4") (pintype "passive"))
      (node (ref "R51") (pin "2") (pinfunction "2_2") (pintype "passive"))
      (node (ref "U4") (pin "B4") (pinfunction "P4_4/JTAG0_TCK_B4") (pintype "bidirectional"))
    )
    (net (code "50") (name "/JTAG_TDI") (class "Default")
      (node (ref "D5") (pin "1") (pinfunction "1_1") (pintype "bidirectional"))
      (node (ref "R49") (pin "1") (pinfunction "1_1") (pintype "passive"))
      (node (ref "U4") (pin "C7") (pinfunction "P4_6/JTAG0_TDI_C7") (pintype "bidirectional"))
    )
    (net (code "51") (name "/JTAG_TDO") (class "Default")
      (node (ref "B7") (pin "3") (pinfunction "CH2_3") (pintype "passive"))
      (node (ref "J5") (pin "6") (pintype "passive"))
      (node (ref "U4") (pin "E11") (pinfunction "P4_7/JTAG0_TDO_E11") (pintype "bidirectional"))
    )
    (net (code "52") (name "/JTAG_TMS") (class "Default")
      (node (ref "B7") (pin "1") (pinfunction "CH1_1") (pintype "passive"))
      (node (ref "J5") (pin "2") (pintype "passive"))
      (node (ref "R50") (pin "1") (pinfunction "1_1") (pintype "passive"))
      (node (ref "U4") (pin "A3") (pinfunction "P4_5/JTAG0_TMS_A3") (pintype "bidirectional"))
    )
    (net (code "53") (name "/LED_B") (class "Default")
      (node (ref "Q3") (pin "3") (pinfunction "D_3") (pintype "bidirectional"))
      (node (ref "R41") (pin "1") (pinfunction "1_1") (pintype "passive"))
    )
    (net (code "54") (name "/LED_B_D") (class "Default")
      (node (ref "D3") (pin "1") (pinfunction "BLUE_1") (pintype "passive"))
      (node (ref "R41") (pin "2") (pinfunction "2_2") (pintype "passive"))
    )
    (net (code "55") (name "/LED_B_INT") (class "Default")
      (node (ref "Q3") (pin "2") (pinfunction "S_2") (pintype "bidirectional"))
      (node (ref "R46") (pin "1") (pinfunction "1_1") (pintype "passive"))
      (node (ref "U4") (pin "F14") (pinfunction "P6_0_F14") (pintype "bidirectional"))
    )
    (net (code "56") (name "/LED_G") (class "Default")
      (node (ref "Q2") (pin "3") (pinfunction "D_3") (pintype "bidirectional"))
      (node (ref "R42") (pin "1") (pinfunction "1_1") (pintype "passive"))
    )
    (net (code "57") (name "/LED_G_D") (class "Default")
      (node (ref "D3") (pin "2") (pinfunction "GREEN_2") (pintype "passive"))
      (node (ref "R42") (pin "2") (pinfunction "2_2") (pintype "passive"))
    )
    (net (code "58") (name "/LED_G_INT") (class "Default")
      (node (ref "Q2") (pin "2") (pinfunction "S_2") (pintype "bidirectional"))
      (node (ref "R45") (pin "1") (pinfunction "1_1") (pintype "passive"))
      (node (ref "U4") (pin "A11") (pinfunction "P6_3_A11") (pintype "bidirectional"))
    )
    (net (code "59") (name "/LED_R") (class "Default")
      (node (ref "Q1") (pin "3") (pinfunction "D_3") (pintype "bidirectional"))
      (node (ref "R43") (pin "1") (pinfunction "1_1") (pintype "passive"))
    )
    (net (code "60") (name "/LED_R_D") (class "Default")
      (node (ref "D3") (pin "3") (pinfunction "RED_3") (pintype "passive"))
      (node (ref "R43") (pin "2") (pinfunction "2_2") (pintype "passive"))
    )
    (net (code "61") (name "/LED_R_INT") (class "Default")
      (node (ref "Q1") (pin "2") (pinfunction "S_2") (pintype "bidirectional"))
      (node (ref "R44") (pin "1") (pinfunction "1_1") (pintype "passive"))
      (node (ref "U4") (pin "L7") (pinfunction "P0_0_L7") (pintype "bidirectional"))
    )
    (net (code "62") (name "/LFXO_N") (class "Default")
      (node (ref "C35") (pin "1") (pinfunction "1_1") (pintype "passive"))
      (node (ref "U4") (pin "P6") (pinfunction "LFXO_N_P6") (pintype "input"))
      (node (ref "Y2") (pin "1") (pinfunction "1_1") (pintype "passive"))
    )
    (net (code "63") (name "/LFXO_P") (class "Default")
      (node (ref "C34") (pin "1") (pinfunction "1_1") (pintype "passive"))
      (node (ref "U4") (pin "R5") (pinfunction "LFXO_P_R5") (pintype "input"))
      (node (ref "Y2") (pin "2") (pinfunction "2_2") (pintype "passive"))
    )
    (net (code "64") (name "/MIPI_R") (class "Default")
      (node (ref "R39") (pin "2") (pinfunction "2_2") (pintype "passive"))
      (node (ref "U4") (pin "J13") (pinfunction "MIPI_REXT_J13") (pintype "passive"))
    )
    (net (code "65") (name "/P0") (class "Default")
      (node (ref "B4") (pin "7") (pinfunction "CH6_7") (pintype "passive"))
      (node (ref "IC4") (pin "7") (pinfunction "B4_7") (pintype "passive"))
      (node (ref "J4") (pin "6") (pinfunction "6_6") (pintype "passive"))
    )
    (net (code "66") (name "/P0_INT") (class "Default")
      (node (ref "IC4") (pin "2") (pinfunction "A1_2") (pintype "passive"))
      (node (ref "U4") (pin "E13") (pinfunction "P5_1_E13") (pintype "bidirectional"))
    )
    (net (code "67") (name "/P1") (class "Default")
      (node (ref "B4") (pin "6") (pinfunction "CH5_6") (pintype "passive"))
      (node (ref "IC4") (pin "8") (pinfunction "B3_8") (pintype "passive"))
      (node (ref "J4") (pin "5") (pinfunction "5_5") (pintype "passive"))
    )
    (net (code "68") (name "/P1_INT") (class "Default")
      (node (ref "IC4") (pin "3") (pinfunction "A2_3") (pintype "passive"))
      (node (ref "U4") (pin "B6") (pinfunction "P5_0_B6") (pintype "bidirectional"))
    )
    (net (code "69") (name "/P2") (class "Default")
      (node (ref "B4") (pin "5") (pinfunction "CH4_5") (pintype "passive"))
      (node (ref "IC4") (pin "9") (pinfunction "B2_9") (pintype "passive"))
      (node (ref "J4") (pin "4") (pinfunction "4_4") (pintype "passive"))
    )
    (net (code "70") (name "/P2_INT") (class "Default")
      (node (ref "IC4") (pin "4") (pinfunction "A3_4") (pintype "passive"))
      (node (ref "U4") (pin "H8") (pinfunction "P1_2_H8") (pintype "bidirectional"))
    )
    (net (code "71") (name "/P3") (class "Default")
      (node (ref "B4") (pin "4") (pinfunction "CH3_4") (pintype "passive"))
      (node (ref "IC4") (pin "10") (pinfunction "B1_10") (pintype "passive"))
      (node (ref "J4") (pin "3") (pinfunction "3_3") (pintype "passive"))
    )
    (net (code "72") (name "/P3_INT") (class "Default")
      (node (ref "IC4") (pin "5") (pinfunction "A4_5") (pintype "passive"))
      (node (ref "U4") (pin "K4") (pinfunction "P1_3_K4") (pintype "bidirectional"))
    )
    (net (code "73") (name "/P6") (class "Default")
      (node (ref "U4") (pin "L19") (pinfunction "P7_5_FLEX_L19") (pintype "bidirectional"))
    )
    (net (code "74") (name "/P7") (class "Default")
      (node (ref "U4") (pin "M22") (pinfunction "P7_4_FLEX_M22") (pintype "bidirectional"))
    )
    (net (code "75") (name "/P8") (class "Default")
      (node (ref "U4") (pin "N27") (pinfunction "P7_6_FLEX_N27") (pintype "bidirectional"))
    )
    (net (code "76") (name "/P9") (class "Default")
      (node (ref "U4") (pin "N25") (pinfunction "P7_7_FLEX_N25") (pintype "bidirectional"))
    )
    (net (code "77") (name "/PDM_MIC_CLK") (class "Default")
      (node (ref "U4") (pin "P22") (pinfunction "P3_6_P22") (pintype "bidirectional"))
    )
    (net (code "78") (name "/PDM_MIC_DATA") (class "Default")
      (node (ref "U4") (pin "R23") (pinfunction "P3_7/JTAG0_TRACECLK_R23") (pintype "bidirectional"))
    )
    (net (code "79") (name "/QWIIC_SCL") (class "Default")
      (node (ref "B6") (pin "8") (pinfunction "B1_8") (pintype "passive"))
      (node (ref "D1") (pin "4") (pinfunction "CATHODE3_4") (pintype "passive"))
      (node (ref "J1") (pin "4") (pinfunction "4_4") (pintype "passive"))
    )
    (net (code "80") (name "/QWIIC_SCL_INT") (class "Default")
      (node (ref "B6") (pin "5") (pinfunction "A1_5") (pintype "passive"))
      (node (ref "U4") (pin "K6") (pinfunction "P0_5_K6") (pintype "bidirectional"))
    )
    (net (code "81") (name "/QWIIC_SDA") (class "Default")
      (node (ref "B6") (pin "1") (pinfunction "B2_1") (pintype "passive"))
      (node (ref "D1") (pin "5") (pinfunction "CATHODE4_5") (pintype "passive"))
      (node (ref "J1") (pin "3") (pinfunction "3_3") (pintype "passive"))
    )
    (net (code "82") (name "/QWIIC_SDA_INT") (class "Default")
      (node (ref "B6") (pin "4") (pinfunction "A2_4") (pintype "passive"))
      (node (ref "U4") (pin "K8") (pinfunction "P0_4_K8") (pintype "bidirectional"))
    )
    (net (code "83") (name "/RECOVERY_MODE") (class "Default")
      (node (ref "D1") (pin "3") (pinfunction "CATHODE2_3") (pintype "passive"))
    )
    (net (code "84") (name "/RST_N") (class "Default")
      (node (ref "C37") (pin "2") (pinfunction "2_2") (pintype "passive"))
      (node (ref "Q4") (pin "2") (pinfunction "S_2") (pintype "bidirectional"))
      (node (ref "R36") (pin "1") (pinfunction "1_1") (pintype "passive"))
      (node (ref "U4") (pin "K10") (pinfunction "POR_N_K10") (pintype "input"))
    )
    (net (code "85") (name "/RST_N_EXT") (class "Default")
      (node (ref "B4") (pin "1") (pinfunction "CH1_1") (pintype "passive"))
      (node (ref "J4") (pin "7") (pinfunction "7_7") (pintype "passive"))
      (node (ref "Q4") (pin "3") (pinfunction "D_3") (pintype "bidirectional"))
      (node (ref "R54") (pin "1") (pinfunction "1_1") (pintype "passive"))
    )
    (net (code "86") (name "/SEUART_RX_INT") (class "Default")
      (node (ref "R34") (pin "1") (pinfunction "1_1") (pintype "passive"))
      (node (ref "U4") (pin "B2") (pinfunction "SEUART_RX_B2") (pintype "input"))
    )
    (net (code "87") (name "/SEUART_TX_INT") (class "Default")
      (node (ref "R35") (pin "1") (pinfunction "1_1") (pintype "passive"))
      (node (ref "U4") (pin "C5") (pinfunction "SEUART_TX_C5") (pintype "output"))
    )
    (net (code "88") (name "/TOF_I2C_GPIO") (class "Default")
      (node (ref "U4") (pin "J25") (pinfunction "P9_3_J25") (pintype "bidirectional"))
    )
    (net (code "89") (name "/TOF_I2C_INT") (class "Default")
      (node (ref "U4") (pin "L17") (pinfunction "P15_6_L17") (pintype "bidirectional"))
    )
    (net (code "90") (name "/TOF_I2C_LPN") (class "Default")
      (node (ref "U4") (pin "G25") (pinfunction "P14_2_G25") (pintype "bidirectional"))
    )
    (net (code "91") (name "/TOF_I2C_PWR_EN") (class "Default")
      (node (ref "U4") (pin "P18") (pinfunction "P14_3_P18") (pintype "bidirectional"))
    )
    (net (code "92") (name "/TOF_I2C_RST") (class "Default")
      (node (ref "U4") (pin "J23") (pinfunction "P9_4_J23") (pintype "bidirectional"))
    )
    (net (code "93") (name "/TOF_I2C_SCL") (class "Default")
      (node (ref "U4") (pin "L3") (pinfunction "P1_1_L3") (pintype "bidirectional"))
    )
    (net (code "94") (name "/TOF_I2C_SDA") (class "Default")
      (node (ref "U4") (pin "L1") (pinfunction "P1_0_L1") (pintype "bidirectional"))
    )
    (net (code "95") (name "/USB_D_N") (class "Default")
      (node (ref "U4") (pin "N15") (pinfunction "USB_DM_N15") (pintype "bidirectional"))
    )
    (net (code "96") (name "/USB_D_P") (class "Default")
      (node (ref "U4") (pin "R15") (pinfunction "USB_DP_R15") (pintype "bidirectional"))
    )
    (net (code "97") (name "/USB_D_SEL") (class "Default")
      (node (ref "U4") (pin "K18") (pinfunction "P15_0_FLEX_K18") (pintype "bidirectional"))
    )
    (net (code "98") (name "/USB_D_SEL_FB") (class "Default")
      (node (ref "U4") (pin "N23") (pinfunction "P15_1_FLEX_N23") (pintype "bidirectional"))
    )
    (net (code "99") (name "/USB_R") (class "Default")
      (node (ref "R38") (pin "1") (pinfunction "1_1") (pintype "passive"))
      (node (ref "U4") (pin "K14") (pinfunction "USB_REXT_K14") (pintype "passive"))
    )
    (net (code "100") (name "/USR_SW") (class "Default")
      (node (ref "B7") (pin "4") (pinfunction "CH3_4") (pintype "passive"))
      (node (ref "R52") (pin "2") (pinfunction "2_2") (pintype "passive"))
      (node (ref "R53") (pin "2") (pinfunction "2_2") (pintype "passive"))
      (node (ref "S2") (pin "1") (pinfunction "NO_1") (pintype "passive"))
      (node (ref "S2") (pin "5") (pinfunction "NO_5") (pintype "passive"))
    )
    (net (code "101") (name "/USR_SW_INT") (class "Default")
      (node (ref "C119") (pin "1") (pinfunction "1_1") (pintype "passive"))
      (node (ref "R53") (pin "1") (pinfunction "1_1") (pintype "passive"))
      (node (ref "U4") (pin "M18") (pinfunction "P15_7_M18") (pintype "bidirectional"))
    )
    (net (code "102") (name "/VREF_P") (class "Default")
      (node (ref "C112") (pin "2") (pinfunction "2_2") (pintype "passive"))
      (node (ref "U4") (pin "M4") (pinfunction "VREF_P_M4") (pintype "passive"))
    )
    (net (code "103") (name "/VREG_AON") (class "Default")
      (node (ref "R48") (pin "2") (pinfunction "2_2") (pintype "passive"))
      (node (ref "U4") (pin "L11") (pinfunction "VREG_AON_L11") (pintype "power_in"))
    )
    (net (code "104") (name "/VREG_AON_INT") (class "Default")
      (node (ref "C113") (pin "2") (pinfunction "2_2") (pintype "passive"))
      (node (ref "R48") (pin "1") (pinfunction "1_1") (pintype "passive"))
    )
    (net (code "105") (name "/VREG_DIG_1V8") (class "Default")
      (node (ref "R47") (pin "1") (pinfunction "1_1") (pintype "passive"))
      (node (ref "U4") (pin "J11") (pinfunction "VREG_DIG_1V8_J11") (pintype "power_in"))
    )
    (net (code "106") (name "/VREG_DIG_1V8_INT") (class "Default")
      (node (ref "C115") (pin "2") (pinfunction "2_2") (pintype "passive"))
      (node (ref "R47") (pin "2") (pinfunction "2_2") (pintype "passive"))
    )
    (net (code "107") (name "/VREG_LP_1V8") (class "Default")
      (node (ref "C114") (pin "2") (pinfunction "2_2") (pintype "passive"))
      (node (ref "U4") (pin "N5") (pinfunction "VREG_LP_1V8_N5") (pintype "power_in"))
    )
    (net (code "108") (name "/VREG_MIPI_0V8") (class "Default")
      (node (ref "C118") (pin "2") (pinfunction "2_2") (pintype "passive"))
      (node (ref "U4") (pin "L13") (pinfunction "VREG_MIPI_0V8_L13") (pintype "power_in"))
    )
    (net (code "109") (name "/VREG_MIPI_1V8") (class "Default")
      (node (ref "C116") (pin "2") (pinfunction "2_2") (pintype "passive"))
      (node (ref "C117") (pin "2") (pinfunction "2_2") (pintype "passive"))
      (node (ref "U4") (pin "G13") (pinfunction "VREG_MIPI_1V8_G13") (pintype "power_in"))
      (node (ref "U4") (pin "M12") (pinfunction "VDD_MIPI_1V8_M12") (pintype "power_in"))
    )
    (net (code "110") (name "/VSW") (class "Default")
      (node (ref "L1") (pin "1") (pinfunction "1_1") (pintype "passive"))
      (node (ref "U4") (pin "P4") (pinfunction "VSW_P4") (pintype "passive"))
      (node (ref "U4") (pin "R1") (pinfunction "VSW_R1") (pintype "passive"))
    )
    (net (code "111") (name "/WIFI_GPIO_1") (class "Default")
      (node (ref "U4") (pin "B8") (pinfunction "P5_2_B8") (pintype "bidirectional"))
    )
    (net (code "112") (name "/WIFI_GPIO_2") (class "Default")
      (node (ref "U4") (pin "A7") (pinfunction "P5_3_A7") (pintype "bidirectional"))
    )
    (net (code "113") (name "/WIFI_I2S_SCLK") (class "Default")
      (node (ref "U4") (pin "C1") (pinfunction "P12_2_C1") (pintype "bidirectional"))
    )
    (net (code "114") (name "/WIFI_I2S_SDI") (class "Default")
      (node (ref "U4") (pin "D2") (pinfunction "P12_0_D2") (pintype "bidirectional"))
    )
    (net (code "115") (name "/WIFI_I2S_SDO") (class "Default")
      (node (ref "U4") (pin "D4") (pinfunction "P12_1_D4") (pintype "bidirectional"))
    )
    (net (code "116") (name "/WIFI_I2S_WS") (class "Default")
      (node (ref "U4") (pin "E7") (pinfunction "P12_3_E7") (pintype "bidirectional"))
    )
    (net (code "117") (name "/WIFI_IRQ") (class "Default")
      (node (ref "U4") (pin "K28") (pinfunction "P9_6_K28") (pintype "bidirectional"))
    )
    (net (code "118") (name "/WIFI_MISO") (class "Default")
      (node (ref "U4") (pin "A15") (pinfunction "P12_4_A15") (pintype "bidirectional"))
    )
    (net (code "119") (name "/WIFI_MOSI") (class "Default")
      (node (ref "U4") (pin "B16") (pinfunction "P12_5_B16") (pintype "bidirectional"))
    )
    (net (code "120") (name "/WIFI_SCLK") (class "Default")
      (node (ref "U4") (pin "F16") (pinfunction "P12_6_F16") (pintype "bidirectional"))
    )
    (net (code "121") (name "/WIFI_SSEL") (class "Default")
      (node (ref "U4") (pin "E17") (pinfunction "P12_7_E17") (pintype "bidirectional"))
    )
    (net (code "122") (name "/WL_H_WAKE") (class "Default")
      (node (ref "U4") (pin "M28") (pinfunction "P11_0_M28") (pintype "bidirectional"))
    )
    (net (code "123") (name "/WL_REG_ON") (class "Default")
      (node (ref "U4") (pin "L27") (pinfunction "P10_4_L27") (pintype "bidirectional"))
    )
    (net (code "124") (name "GND") (class "Default")
      (node (ref "B4") (pin "2") (pinfunction "GND_2") (pintype "passive"))
      (node (ref "B6") (pin "2") (pinfunction "GND_2") (pintype "passive"))
      (node (ref "B7") (pin "2") (pinfunction "GND_2") (pintype "passive"))
      (node (ref "C100") (pin "1") (pinfunction "1_1") (pintype "passive"))
      (node (ref "C101") (pin "1") (pinfunction "1_1") (pintype "passive"))
      (node (ref "C102") (pin "2") (pinfunction "2_2") (pintype "passive"))
      (node (ref "C103") (pin "1") (pinfunction "1_1") (pintype "passive"))
      (node (ref "C104") (pin "1") (pinfunction "1_1") (pintype "passive"))
      (node (ref "C105") (pin "2") (pinfunction "2_2") (pintype "passive"))
      (node (ref "C106") (pin "1") (pinfunction "1_1") (pintype "passive"))
      (node (ref "C107") (pin "1") (pinfunction "1_1") (pintype "passive"))
      (node (ref "C108") (pin "1") (pinfunction "1_1") (pintype "passive"))
      (node (ref "C109") (pin "2") (pinfunction "2_2") (pintype "passive"))
      (node (ref "C110") (pin "2") (pinfunction "2_2") (pintype "passive"))
      (node (ref "C111") (pin "1") (pinfunction "1_1") (pintype "passive"))
      (node (ref "C112") (pin "1") (pinfunction "1_1") (pintype "passive"))
      (node (ref "C113") (pin "1") (pinfunction "1_1") (pintype "passive"))
      (node (ref "C114") (pin "1") (pinfunction "1_1") (pintype "passive"))
      (node (ref "C115") (pin "1") (pinfunction "1_1") (pintype "passive"))
      (node (ref "C116") (pin "1") (pinfunction "1_1") (pintype "passive"))
      (node (ref "C117") (pin "1") (pinfunction "1_1") (pintype "passive"))
      (node (ref "C118") (pin "1") (pinfunction "1_1") (pintype "passive"))
      (node (ref "C119") (pin "2") (pinfunction "2_2") (pintype "passive"))
      (node (ref "C121") (pin "1") (pinfunction "1_1") (pintype "passive"))
      (node (ref "C122") (pin "1") (pinfunction "1_1") (pintype "passive"))
      (node (ref "C20") (pin "1") (pinfunction "1_1") (pintype "passive"))
      (node (ref "C22") (pin "1") (pinfunction "1_1") (pintype "passive"))
      (node (ref "C34") (pin "2") (pinfunction "2_2") (pintype "passive"))
      (node (ref "C35") (pin "2") (pinfunction "2_2") (pintype "passive"))
      (node (ref "C37") (pin "1") (pinfunction "1_1") (pintype "passive"))
      (node (ref "C38") (pin "1") (pinfunction "1_1") (pintype "passive"))
      (node (ref "C84") (pin "1") (pinfunction "1_1") (pintype "passive"))
      (node (ref "C85") (pin "1") (pinfunction "1_1") (pintype "passive"))
      (node (ref "C86") (pin "2") (pinfunction "2_2") (pintype "passive"))
      (node (ref "C87") (pin "2") (pinfunction "2_2") (pintype "passive"))
      (node (ref "C88") (pin "1") (pinfunction "1_1") (pintype "passive"))
      (node (ref "C89") (pin "2") (pinfunction "2_2") (pintype "passive"))
      (node (ref "C90") (pin "1") (pinfunction "1_1") (pintype "passive"))
      (node (ref "C91") (pin "1") (pinfunction "1_1") (pintype "passive"))
      (node (ref "C92") (pin "2") (pinfunction "2_2") (pintype "passive"))
      (node (ref "C93") (pin "1") (pinfunction "1_1") (pintype "passive"))
      (node (ref "C94") (pin "1") (pinfunction "1_1") (pintype "passive"))
      (node (ref "C95") (pin "2") (pinfunction "2_2") (pintype "passive"))
      (node (ref "C96") (pin "1") (pinfunction "1_1") (pintype "passive"))
      (node (ref "C97") (pin "1") (pinfunction "1_1") (pintype "passive"))
      (node (ref "C98") (pin "1") (pinfunction "1_1") (pintype "passive"))
      (node (ref "C99") (pin "1") (pinfunction "1_1") (pintype "passive"))
      (node (ref "D1") (pin "2") (pinfunction "ANODE_2") (pintype "passive"))
      (node (ref "D5") (pin "2") (pinfunction "2_2") (pintype "bidirectional"))
      (node (ref "IC4") (pin "6") (pinfunction "GND_6") (pintype "passive"))
      (node (ref "J1") (pin "1") (pinfunction "1_1") (pintype "passive"))
      (node (ref "J1") (pin "S1") (pinfunction "SHIELD_S1") (pintype "passive"))
      (node (ref "J1") (pin "S2") (pinfunction "SHIELD_S2") (pintype "passive"))
      (node (ref "J4") (pin "1") (pinfunction "1_1") (pintype "passive"))
      (node (ref "J5") (pin "5") (pintype "passive"))
      (node (ref "R38") (pin "2") (pinfunction "2_2") (pintype "passive"))
      (node (ref "R39") (pin "1") (pinfunction "1_1") (pintype "passive"))
      (node (ref "R51") (pin "1") (pinfunction "1_1") (pintype "passive"))
      (node (ref "S2") (pin "2") (pinfunction "COM_2") (pintype "passive"))
      (node (ref "S2") (pin "3") (pinfunction "COM_3") (pintype "passive"))
      (node (ref "S2") (pin "4") (pinfunction "COM_4") (pintype "passive"))
      (node (ref "U4") (pin "B12") (pinfunction "VSS_B12") (pintype "power_in"))
      (node (ref "U4") (pin "B22") (pinfunction "VSS_B22") (pintype "power_in"))
      (node (ref "U4") (pin "B24") (pinfunction "VSS_B24") (pintype "power_in"))
      (node (ref "U4") (pin "C3") (pinfunction "RESERVED_C3") (pintype "input"))
      (node (ref "U4") (pin "D22") (pinfunction "VSS_D22") (pintype "power_in"))
      (node (ref "U4") (pin "E25") (pinfunction "VSS_E25") (pintype "power_in"))
      (node (ref "U4") (pin "E27") (pinfunction "VSS_E27") (pintype "power_in"))
      (node (ref "U4") (pin "F26") (pinfunction "VSS_F26") (pintype "power_in"))
      (node (ref "U4") (pin "G1") (pinfunction "VSS_G1") (pintype "power_in"))
      (node (ref "U4") (pin "H26") (pinfunction "VSS_H26") (pintype "power_in"))
      (node (ref "U4") (pin "L9") (pinfunction "VSS_L9") (pintype "power_in"))
      (node (ref "U4") (pin "M2") (pinfunction "VREF_N_M2") (pintype "passive"))
      (node (ref "U4") (pin "M20") (pinfunction "VSS_M20") (pintype "power_in"))
      (node (ref "U4") (pin "N1") (pinfunction "VSS_ANA_N1") (pintype "power_in"))
      (node (ref "U4") (pin "R13") (pinfunction "VSS_R13") (pintype "power_in"))
      (node (ref "U4") (pin "R25") (pinfunction "VSS_R25") (pintype "power_in"))
      (node (ref "U4") (pin "R3") (pinfunction "VSS_BUCK_R3") (pintype "power_in"))
      (node (ref "U4") (pin "R9") (pinfunction "VSS_R9") (pintype "power_in"))
      (node (ref "X1") (pin "2") (pinfunction "NO_CONNECT_1_2") (pintype "passive"))
      (node (ref "X1") (pin "4") (pinfunction "NO_CONNECT_2_4") (pintype "passive"))
    )
    (net (code "125") (name "VBUS") (class "Default")
      (node (ref "U4") (pin "H14") (pinfunction "USB_VBUS_H14") (pintype "input"))
    )
    (net (code "126") (name "VCC_1.8V") (class "Default")
      (node (ref "B6") (pin "3") (pinfunction "VCC(A)_3") (pintype "passive"))
      (node (ref "B6") (pin "6") (pinfunction "OE_6") (pintype "passive"))
      (node (ref "B7") (pin "5") (pinfunction "CH4_5") (pintype "passive"))
      (node (ref "C104") (pin "2") (pinfunction "2_2") (pintype "passive"))
      (node (ref "C105") (pin "1") (pinfunction "1_1") (pintype "passive"))
      (node (ref "C106") (pin "2") (pinfunction "2_2") (pintype "passive"))
      (node (ref "C107") (pin "2") (pinfunction "2_2") (pintype "passive"))
      (node (ref "C108") (pin "2") (pinfunction "2_2") (pintype "passive"))
      (node (ref "C121") (pin "2") (pinfunction "2_2") (pintype "passive"))
      (node (ref "C84") (pin "2") (pinfunction "2_2") (pintype "passive"))
      (node (ref "IC4") (pin "1") (pinfunction "VCC(A)_1") (pintype "passive"))
      (node (ref "IC4") (pin "12") (pinfunction "OE_12") (pintype "passive"))
      (node (ref "J5") (pin "1") (pintype "passive"))
      (node (ref "Q1") (pin "1") (pinfunction "G_1") (pintype "bidirectional"))
      (node (ref "Q2") (pin "1") (pinfunction "G_1") (pintype "bidirectional"))
      (node (ref "Q3") (pin "1") (pinfunction "G_1") (pintype "bidirectional"))
      (node (ref "Q4") (pin "1") (pinfunction "G_1") (pintype "bidirectional"))
      (node (ref "R34") (pin "2") (pinfunction "2_2") (pintype "passive"))
      (node (ref "R35") (pin "2") (pinfunction "2_2") (pintype "passive"))
      (node (ref "R36") (pin "2") (pinfunction "2_2") (pintype "passive"))
      (node (ref "R37") (pin "2") (pinfunction "2_2") (pintype "passive"))
      (node (ref "R44") (pin "2") (pinfunction "2_2") (pintype "passive"))
      (node (ref "R45") (pin "2") (pinfunction "2_2") (pintype "passive"))
      (node (ref "R46") (pin "2") (pinfunction "2_2") (pintype "passive"))
      (node (ref "R49") (pin "2") (pinfunction "2_2") (pintype "passive"))
      (node (ref "R50") (pin "2") (pinfunction "2_2") (pintype "passive"))
      (node (ref "R52") (pin "1") (pinfunction "1_1") (pintype "passive"))
      (node (ref "U4") (pin "C13") (pinfunction "VDD_IO_1V8_C13") (pintype "power_in"))
      (node (ref "U4") (pin "F4") (pinfunction "VDD_IO_1V8_F4") (pintype "power_in"))
      (node (ref "U4") (pin "P24") (pinfunction "VDD_IO_1V8_P24") (pintype "power_in"))
    )
    (net (code "127") (name "VCC_3.3V") (class "Default")
      (node (ref "B4") (pin "3") (pinfunction "CH2_3") (pintype "passive"))
      (node (ref "B6") (pin "7") (pinfunction "VCC(B)_7") (pintype "passive"))
      (node (ref "C102") (pin "1") (pinfunction "1_1") (pintype "passive"))
      (node (ref "C103") (pin "2") (pinfunction "2_2") (pintype "passive"))
      (node (ref "C110") (pin "1") (pinfunction "1_1") (pintype "passive"))
      (node (ref "C111") (pin "2") (pinfunction "2_2") (pintype "passive"))
      (node (ref "C122") (pin "2") (pinfunction "2_2") (pintype "passive"))
      (node (ref "C85") (pin "2") (pinfunction "2_2") (pintype "passive"))
      (node (ref "C88") (pin "2") (pinfunction "2_2") (pintype "passive"))
      (node (ref "C89") (pin "1") (pinfunction "1_1") (pintype "passive"))
      (node (ref "C90") (pin "2") (pinfunction "2_2") (pintype "passive"))
      (node (ref "C91") (pin "2") (pinfunction "2_2") (pintype "passive"))
      (node (ref "C92") (pin "1") (pinfunction "1_1") (pintype "passive"))
      (node (ref "C93") (pin "2") (pinfunction "2_2") (pintype "passive"))
      (node (ref "C94") (pin "2") (pinfunction "2_2") (pintype "passive"))
      (node (ref "C95") (pin "1") (pinfunction "1_1") (pintype "passive"))
      (node (ref "C96") (pin "2") (pinfunction "2_2") (pintype "passive"))
      (node (ref "D1") (pin "1") (pinfunction "CATHODE_1_1") (pintype "passive"))
      (node (ref "D3") (pin "4") (pinfunction "ANODE_4") (pintype "passive"))
      (node (ref "IC4") (pin "11") (pinfunction "VCC(B)_11") (pintype "passive"))
      (node (ref "J1") (pin "2") (pinfunction "2_2") (pintype "passive"))
      (node (ref "J4") (pin "2") (pinfunction "2_2") (pintype "passive"))
      (node (ref "R54") (pin "2") (pinfunction "2_2") (pintype "passive"))
      (node (ref "U4") (pin "K12") (pinfunction "VDD_BATT_K12") (pintype "power_in"))
      (node (ref "U4") (pin "L5") (pinfunction "VDD_MAIN_L5") (pintype "power_in"))
      (node (ref "U4") (pin "P14") (pinfunction "VDD_USB_3V3_P14") (pintype "power_in"))
      (node (ref "U4") (pin "P2") (pinfunction "VDD_BUCK_P2") (pintype "power_in"))
      (node (ref "U4") (pin "P28") (pinfunction "VDD_IO_FLEX_P28") (pintype "power_in"))
    )
    (net (code "128") (name "VDD_CORE") (class "Default")
      (node (ref "C100") (pin "2") (pinfunction "2_2") (pintype "passive"))
      (node (ref "C101") (pin "2") (pinfunction "2_2") (pintype "passive"))
      (node (ref "C109") (pin "1") (pinfunction "1_1") (pintype "passive"))
      (node (ref "C86") (pin "1") (pinfunction "1_1") (pintype "passive"))
      (node (ref "C87") (pin "1") (pinfunction "1_1") (pintype "passive"))
      (node (ref "C97") (pin "2") (pinfunction "2_2") (pintype "passive"))
      (node (ref "C98") (pin "2") (pinfunction "2_2") (pintype "passive"))
      (node (ref "C99") (pin "2") (pinfunction "2_2") (pintype "passive"))
      (node (ref "L1") (pin "2") (pinfunction "2_2") (pintype "passive"))
      (node (ref "U4") (pin "A13") (pinfunction "VDD_CORE_0V8_A13") (pintype "power_in"))
      (node (ref "U4") (pin "C21") (pinfunction "VDD_SX_0V8_C21") (pintype "power_in"))
      (node (ref "U4") (pin "C25") (pinfunction "VDD_PLL_0V8_C25") (pintype "power_in"))
      (node (ref "U4") (pin "G3") (pinfunction "VDD_CORE_0V8_G3") (pintype "power_in"))
      (node (ref "U4") (pin "H24") (pinfunction "VDD_CORE_0V8_H24") (pintype "power_in"))
      (node (ref "U4") (pin "M6") (pinfunction "VREG_CORE_0V8_M6") (pintype "power_in"))
      (node (ref "U4") (pin "N17") (pinfunction "VDD_CORE_0V8_N17") (pintype "power_in"))
    )
    (net (code "129") (name "unconnected-(U4A-nc-PadC15)") (class "Default")
      (node (ref "U4") (pin "C15") (pinfunction "nc_C15") (pintype "power_in+no_connect"))
    )
    (net (code "130") (name "unconnected-(U4A-nc-PadC23)") (class "Default")
      (node (ref "U4") (pin "C23") (pinfunction "nc_C23") (pintype "power_in+no_connect"))
    )
    (net (code "131") (name "unconnected-(U4A-nc-PadD26)") (class "Default")
      (node (ref "U4") (pin "D26") (pinfunction "nc_D26") (pintype "power_in+no_connect"))
    )
    (net (code "132") (name "unconnected-(U4A-nc-PadF24)") (class "Default")
      (node (ref "U4") (pin "F24") (pinfunction "nc_F24") (pintype "power_in+no_connect"))
    )
    (net (code "133") (name "unconnected-(U4B-AMUX_N-PadE21)") (class "Default")
      (node (ref "U4") (pin "E21") (pinfunction "AMUX_N_E21") (pintype "passive+no_connect"))
    )
    (net (code "134") (name "unconnected-(U4B-AMUX_P-PadE23)") (class "Default")
      (node (ref "U4") (pin "E23") (pinfunction "AMUX_P_E23") (pintype "passive+no_connect"))
    )
    (net (code "135") (name "unconnected-(U4B-AMUX_PMU-PadG11)") (class "Default")
      (node (ref "U4") (pin "G11") (pinfunction "AMUX_PMU_G11") (pintype "passive+no_connect"))
    )
    (net (code "136") (name "unconnected-(U4B-nc-PadB26)") (class "Default")
      (node (ref "U4") (pin "B26") (pinfunction "nc_B26") (pintype "input+no_connect"))
    )
    (net (code "137") (name "unconnected-(U4B-nc-PadB28)") (class "Default")
      (node (ref "U4") (pin "B28") (pinfunction "nc_B28") (pintype "input+no_connect"))
    )
    (net (code "138") (name "unconnected-(U4B-nc-PadC27)") (class "Default")
      (node (ref "U4") (pin "C27") (pinfunction "nc_C27") (pintype "input+no_connect"))
    )
    (net (code "139") (name "unconnected-(U4B-nc-PadD28)") (class "Default")
      (node (ref "U4") (pin "D28") (pinfunction "nc_D28") (pintype "output+no_connect"))
    )
    (net (code "140") (name "unconnected-(U4B-nc-PadF28)") (class "Default")
      (node (ref "U4") (pin "F28") (pinfunction "nc_F28") (pintype "output+no_connect"))
    )
    (net (code "141") (name "unconnected-(U4C-P0_1-PadH12)") (class "Default")
      (node (ref "U4") (pin "H12") (pinfunction "P0_1_H12") (pintype "bidirectional+no_connect"))
    )
    (net (code "142") (name "unconnected-(U4C-P0_2-PadJ9)") (class "Default")
      (node (ref "U4") (pin "J9") (pinfunction "P0_2_J9") (pintype "bidirectional+no_connect"))
    )
    (net (code "143") (name "unconnected-(U4C-P0_3-PadN3)") (class "Default")
      (node (ref "U4") (pin "N3") (pinfunction "P0_3_N3") (pintype "bidirectional+no_connect"))
    )
    (net (code "144") (name "unconnected-(U4C-P0_6-PadH10)") (class "Default")
      (node (ref "U4") (pin "H10") (pinfunction "P0_6_H10") (pintype "bidirectional+no_connect"))
    )
    (net (code "145") (name "unconnected-(U4C-P0_7-PadJ7)") (class "Default")
      (node (ref "U4") (pin "J7") (pinfunction "P0_7_J7") (pintype "bidirectional+no_connect"))
    )
    (net (code "146") (name "unconnected-(U4C-P4_2{slash}JTAG0_TDATA2-PadE9)") (class "Default")
      (node (ref "U4") (pin "E9") (pinfunction "P4_2/JTAG0_TDATA2_E9") (pintype "bidirectional+no_connect"))
    )
    (net (code "147") (name "unconnected-(U4C-P4_3{slash}JTAG0_TDATA3-PadD8)") (class "Default")
      (node (ref "U4") (pin "D8") (pinfunction "P4_3/JTAG0_TDATA3_D8") (pintype "bidirectional+no_connect"))
    )
    (net (code "148") (name "unconnected-(U4C-P5_4-PadD12)") (class "Default")
      (node (ref "U4") (pin "D12") (pinfunction "P5_4_D12") (pintype "bidirectional+no_connect"))
    )
    (net (code "149") (name "unconnected-(U4C-P5_5-PadC11)") (class "Default")
      (node (ref "U4") (pin "C11") (pinfunction "P5_5_C11") (pintype "bidirectional+no_connect"))
    )
    (net (code "150") (name "unconnected-(U4C-P5_6-PadB10)") (class "Default")
      (node (ref "U4") (pin "B10") (pinfunction "P5_6_B10") (pintype "bidirectional+no_connect"))
    )
    (net (code "151") (name "unconnected-(U4C-P6_1-PadE15)") (class "Default")
      (node (ref "U4") (pin "E15") (pinfunction "P6_1_E15") (pintype "bidirectional+no_connect"))
    )
    (net (code "152") (name "unconnected-(U4C-P6_2-PadD14)") (class "Default")
      (node (ref "U4") (pin "D14") (pinfunction "P6_2_D14") (pintype "bidirectional+no_connect"))
    )
    (net (code "153") (name "unconnected-(U4C-P6_4-PadB14)") (class "Default")
      (node (ref "U4") (pin "B14") (pinfunction "P6_4_B14") (pintype "bidirectional+no_connect"))
    )
    (net (code "154") (name "unconnected-(U4C-P6_5-PadG15)") (class "Default")
      (node (ref "U4") (pin "G15") (pinfunction "P6_5_G15") (pintype "bidirectional+no_connect"))
    )
    (net (code "155") (name "unconnected-(U4C-P7_0-PadB18)") (class "Default")
      (node (ref "U4") (pin "B18") (pinfunction "P7_0_B18") (pintype "bidirectional+no_connect"))
    )
    (net (code "156") (name "unconnected-(U4C-P7_1-PadD18)") (class "Default")
      (node (ref "U4") (pin "D18") (pinfunction "P7_1_D18") (pintype "bidirectional+no_connect"))
    )
    (net (code "157") (name "unconnected-(U4C-P7_2-PadF18)") (class "Default")
      (node (ref "U4") (pin "F18") (pinfunction "P7_2_F18") (pintype "bidirectional+no_connect"))
    )
    (net (code "158") (name "unconnected-(U4C-P7_3-PadA19)") (class "Default")
      (node (ref "U4") (pin "A19") (pinfunction "P7_3_A19") (pintype "bidirectional+no_connect"))
    )
    (net (code "159") (name "unconnected-(U4C-P9_0-PadH18)") (class "Default")
      (node (ref "U4") (pin "H18") (pinfunction "P9_0_H18") (pintype "bidirectional+no_connect"))
    )
    (net (code "160") (name "unconnected-(U4C-P9_1-PadH16)") (class "Default")
      (node (ref "U4") (pin "H16") (pinfunction "P9_1_H16") (pintype "bidirectional+no_connect"))
    )
    (net (code "161") (name "unconnected-(U4C-P9_5-PadJ21)") (class "Default")
      (node (ref "U4") (pin "J21") (pinfunction "P9_5_J21") (pintype "bidirectional+no_connect"))
    )
    (net (code "162") (name "unconnected-(U4C-P9_7-PadJ19)") (class "Default")
      (node (ref "U4") (pin "J19") (pinfunction "P9_7_J19") (pintype "bidirectional+no_connect"))
    )
    (net (code "163") (name "unconnected-(U4C-P10_5-PadL25)") (class "Default")
      (node (ref "U4") (pin "L25") (pinfunction "P10_5_L25") (pintype "bidirectional+no_connect"))
    )
    (net (code "164") (name "unconnected-(U4C-P10_6-PadL23)") (class "Default")
      (node (ref "U4") (pin "L23") (pinfunction "P10_6_L23") (pintype "bidirectional+no_connect"))
    )
    (net (code "165") (name "unconnected-(U4C-P10_7-PadL21)") (class "Default")
      (node (ref "U4") (pin "L21") (pinfunction "P10_7_L21") (pintype "bidirectional+no_connect"))
    )
    (net (code "166") (name "unconnected-(U4C-P11_1-PadJ17)") (class "Default")
      (node (ref "U4") (pin "J17") (pinfunction "P11_1_J17") (pintype "bidirectional+no_connect"))
    )
    (net (code "167") (name "unconnected-(U4C-P11_2-PadM26)") (class "Default")
      (node (ref "U4") (pin "M26") (pinfunction "P11_2_M26") (pintype "bidirectional+no_connect"))
    )
    (net (code "168") (name "unconnected-(U4C-P11_3-PadM24)") (class "Default")
      (node (ref "U4") (pin "M24") (pinfunction "P11_3_M24") (pintype "bidirectional+no_connect"))
    )
    (net (code "169") (name "unconnected-(U4C-P13_2-PadF8)") (class "Default")
      (node (ref "U4") (pin "F8") (pinfunction "P13_2_F8") (pintype "bidirectional+no_connect"))
    )
    (net (code "170") (name "unconnected-(U4C-P13_4-PadE3)") (class "Default")
      (node (ref "U4") (pin "E3") (pinfunction "P13_4_E3") (pintype "bidirectional+no_connect"))
    )
    (net (code "171") (name "unconnected-(U4C-P13_5-PadA5)") (class "Default")
      (node (ref "U4") (pin "A5") (pinfunction "P13_5_A5") (pintype "bidirectional+no_connect"))
    )
    (net (code "172") (name "unconnected-(U4C-P13_6-PadD10)") (class "Default")
      (node (ref "U4") (pin "D10") (pinfunction "P13_6_D10") (pintype "bidirectional+no_connect"))
    )
    (net (code "173") (name "unconnected-(U4C-P13_7-PadC9)") (class "Default")
      (node (ref "U4") (pin "C9") (pinfunction "P13_7_C9") (pintype "bidirectional+no_connect"))
    )
    (net (code "174") (name "unconnected-(U4C-P14_0-PadA17)") (class "Default")
      (node (ref "U4") (pin "A17") (pinfunction "P14_0_A17") (pintype "bidirectional+no_connect"))
    )
    (net (code "175") (name "unconnected-(U4C-P14_1-PadG27)") (class "Default")
      (node (ref "U4") (pin "G27") (pinfunction "P14_1_G27") (pintype "bidirectional+no_connect"))
    )
    (net (code "176") (name "unconnected-(U4C-P14_4-PadR19)") (class "Default")
      (node (ref "U4") (pin "R19") (pinfunction "P14_4_R19") (pintype "bidirectional+no_connect"))
    )
    (net (code "177") (name "unconnected-(U4C-P14_5-PadM16)") (class "Default")
      (node (ref "U4") (pin "M16") (pinfunction "P14_5_M16") (pintype "bidirectional+no_connect"))
    )
    (net (code "178") (name "unconnected-(U4C-P14_6-PadL15)") (class "Default")
      (node (ref "U4") (pin "L15") (pinfunction "P14_6_L15") (pintype "bidirectional+no_connect"))
    )
    (net (code "179") (name "unconnected-(U4C-P14_7-PadR17)") (class "Default")
      (node (ref "U4") (pin "R17") (pinfunction "P14_7_R17") (pintype "bidirectional+no_connect"))
    )
    (net (code "180") (name "unconnected-(U4C-P15_2_FLEX-PadN21)") (class "Default")
      (node (ref "U4") (pin "N21") (pinfunction "P15_2_FLEX_N21") (pintype "bidirectional+no_connect"))
    )
    (net (code "181") (name "unconnected-(U4C-P15_3_FLEX-PadP26)") (class "Default")
      (node (ref "U4") (pin "P26") (pinfunction "P15_3_FLEX_P26") (pintype "bidirectional+no_connect"))
    )
    (net (code "182") (name "unconnected-(U4D-MIPICSI_0_N-PadR7)") (class "Default")
      (node (ref "U4") (pin "R7") (pinfunction "MIPICSI_0_N_R7") (pintype "bidirectional+no_connect"))
    )
    (net (code "183") (name "unconnected-(U4D-MIPICSI_0_P-PadP8)") (class "Default")
      (node (ref "U4") (pin "P8") (pinfunction "MIPICSI_0_P_P8") (pintype "bidirectional+no_connect"))
    )
    (net (code "184") (name "unconnected-(U4D-MIPICSI_1_N-PadN9)") (class "Default")
      (node (ref "U4") (pin "N9") (pinfunction "MIPICSI_1_N_N9") (pintype "bidirectional+no_connect"))
    )
    (net (code "185") (name "unconnected-(U4D-MIPICSI_1_P-PadM10)") (class "Default")
      (node (ref "U4") (pin "M10") (pinfunction "MIPICSI_1_P_M10") (pintype "bidirectional+no_connect"))
    )
    (net (code "186") (name "unconnected-(U4D-MIPICSI_C_N-PadN7)") (class "Default")
      (node (ref "U4") (pin "N7") (pinfunction "MIPICSI_C_N_N7") (pintype "output+no_connect"))
    )
    (net (code "187") (name "unconnected-(U4D-MIPICSI_C_P-PadM8)") (class "Default")
      (node (ref "U4") (pin "M8") (pinfunction "MIPICSI_C_P_M8") (pintype "output+no_connect"))
    )
    (net (code "188") (name "unconnected-(U4D-MIPIDSI_0_N-PadN11)") (class "Default")
      (node (ref "U4") (pin "N11") (pinfunction "MIPIDSI_0_N_N11") (pintype "bidirectional+no_connect"))
    )
    (net (code "189") (name "unconnected-(U4D-MIPIDSI_0_P-PadP10)") (class "Default")
      (node (ref "U4") (pin "P10") (pinfunction "MIPIDSI_0_P_P10") (pintype "bidirectional+no_connect"))
    )
    (net (code "190") (name "unconnected-(U4D-MIPIDSI_1_N-PadM14)") (class "Default")
      (node (ref "U4") (pin "M14") (pinfunction "MIPIDSI_1_N_M14") (pintype "bidirectional+no_connect"))
    )
    (net (code "191") (name "unconnected-(U4D-MIPIDSI_1_P-PadN13)") (class "Default")
      (node (ref "U4") (pin "N13") (pinfunction "MIPIDSI_1_P_N13") (pintype "bidirectional+no_connect"))
    )
    (net (code "192") (name "unconnected-(U4D-MIPIDSI_C_N-PadP12)") (class "Default")
      (node (ref "U4") (pin "P12") (pinfunction "MIPIDSI_C_N_P12") (pintype "output+no_connect"))
    )
    (net (code "193") (name "unconnected-(U4D-MIPIDSI_C_P-PadR11)") (class "Default")
      (node (ref "U4") (pin "R11") (pinfunction "MIPIDSI_C_P_R11") (pintype "output+no_connect"))
    )
    (net (code "194") (name "unconnected-(U4D-USB_IO_ID-PadP16)") (class "Default")
      (node (ref "U4") (pin "P16") (pinfunction "USB_IO_ID_P16") (pintype "input+no_connect"))
    )
  )
)
